# TIDA050024.net
KiCad netlist of a schematic drawn in Altium Designer
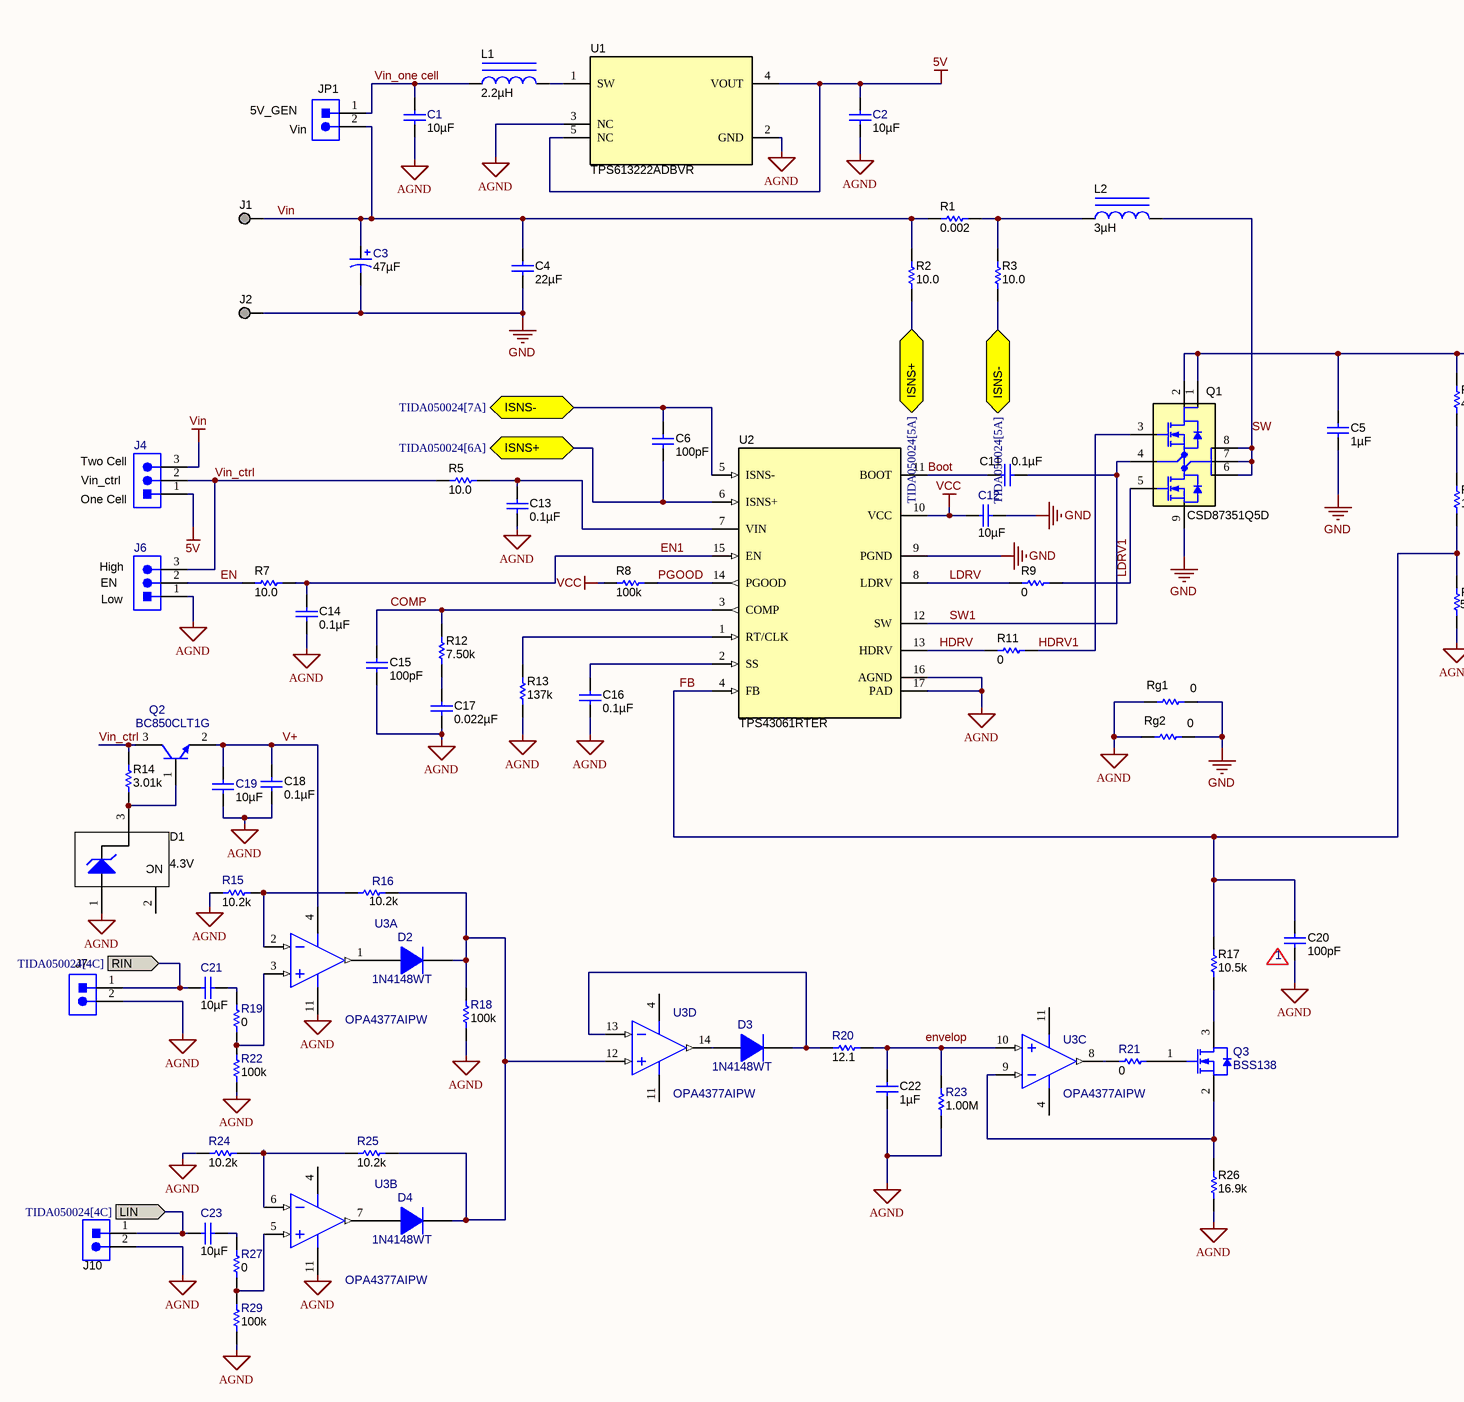
[diagram p0: TIDA050024.SchDoc, top middle]
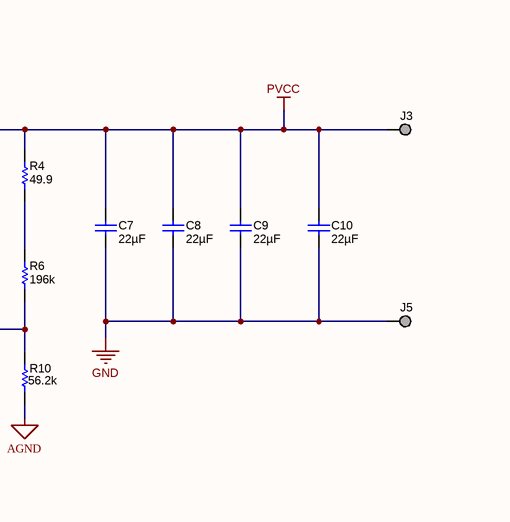
[diagram p1: TIDA050024.SchDoc, top right]
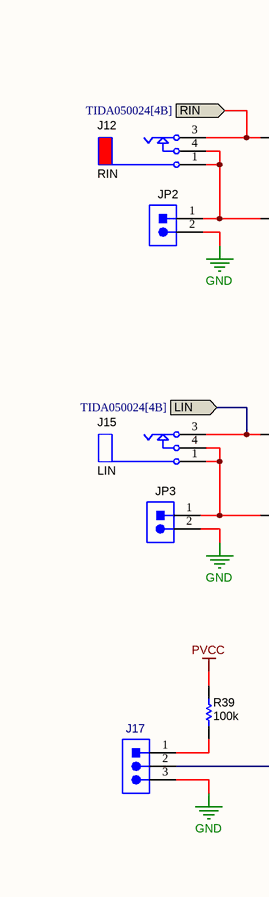
[diagram p2: TIDA050024.SchDoc, bottom left]
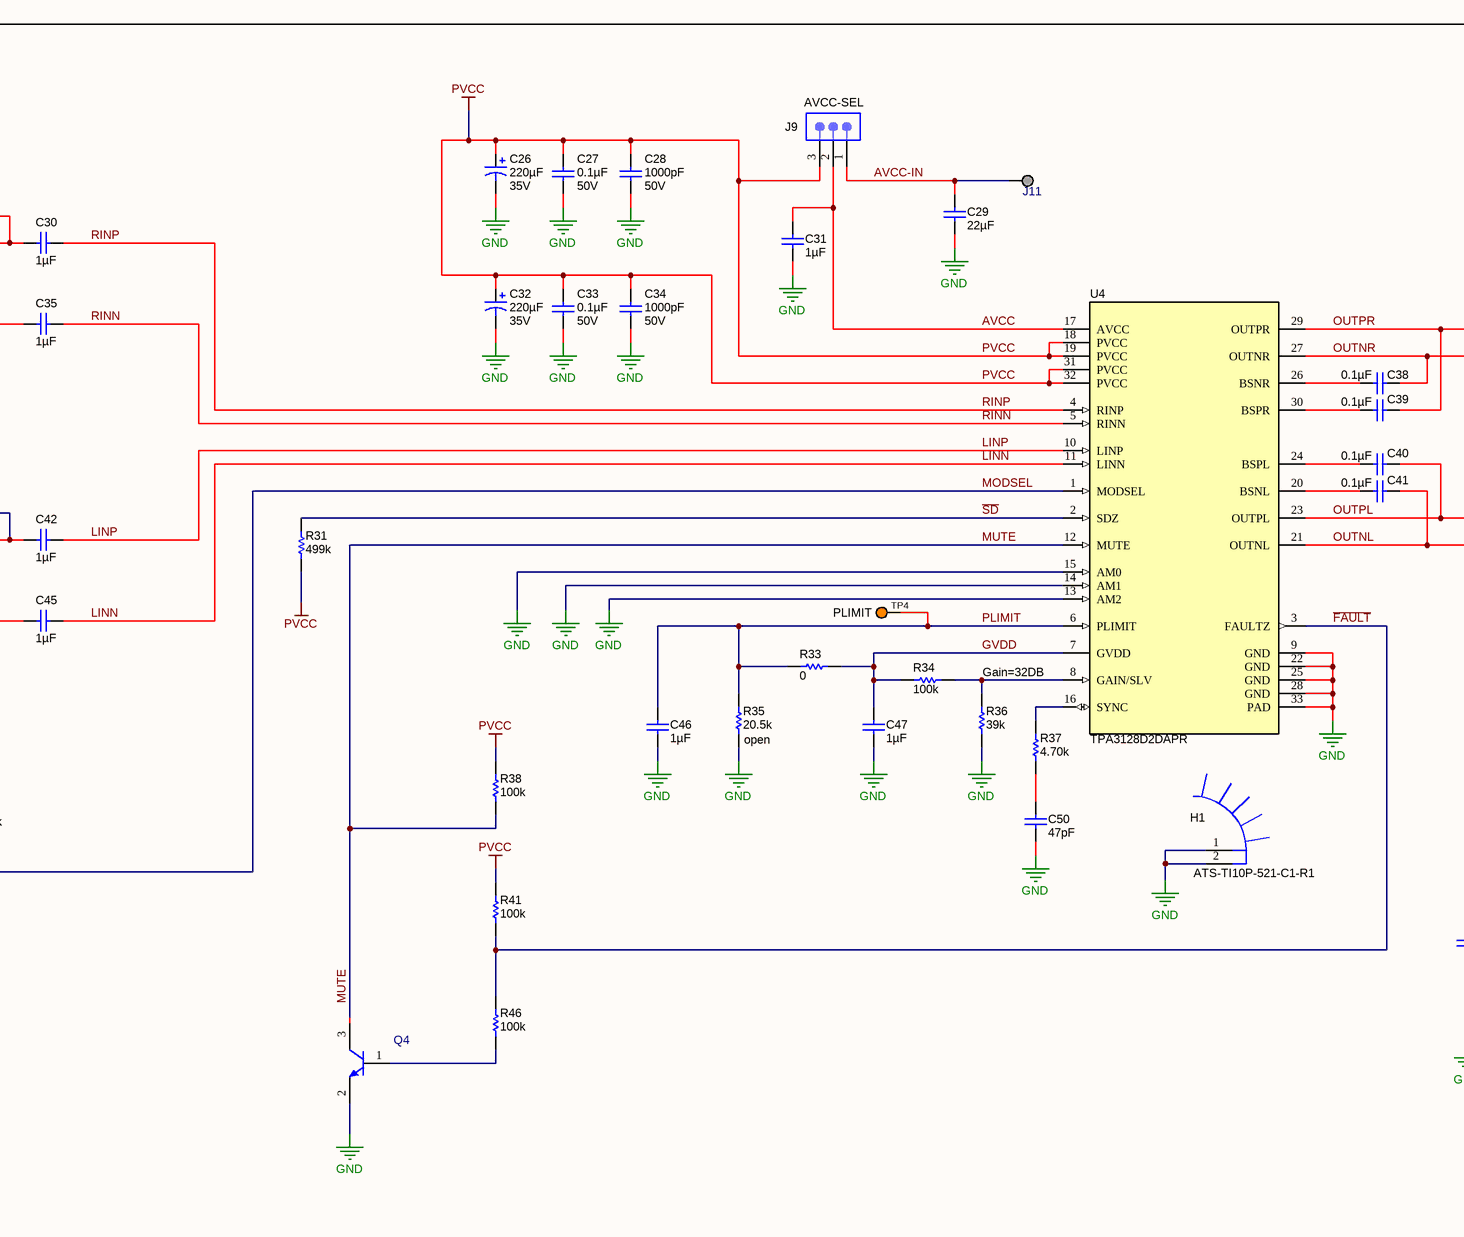
[diagram p3: TIDA050024.SchDoc, bottom middle]
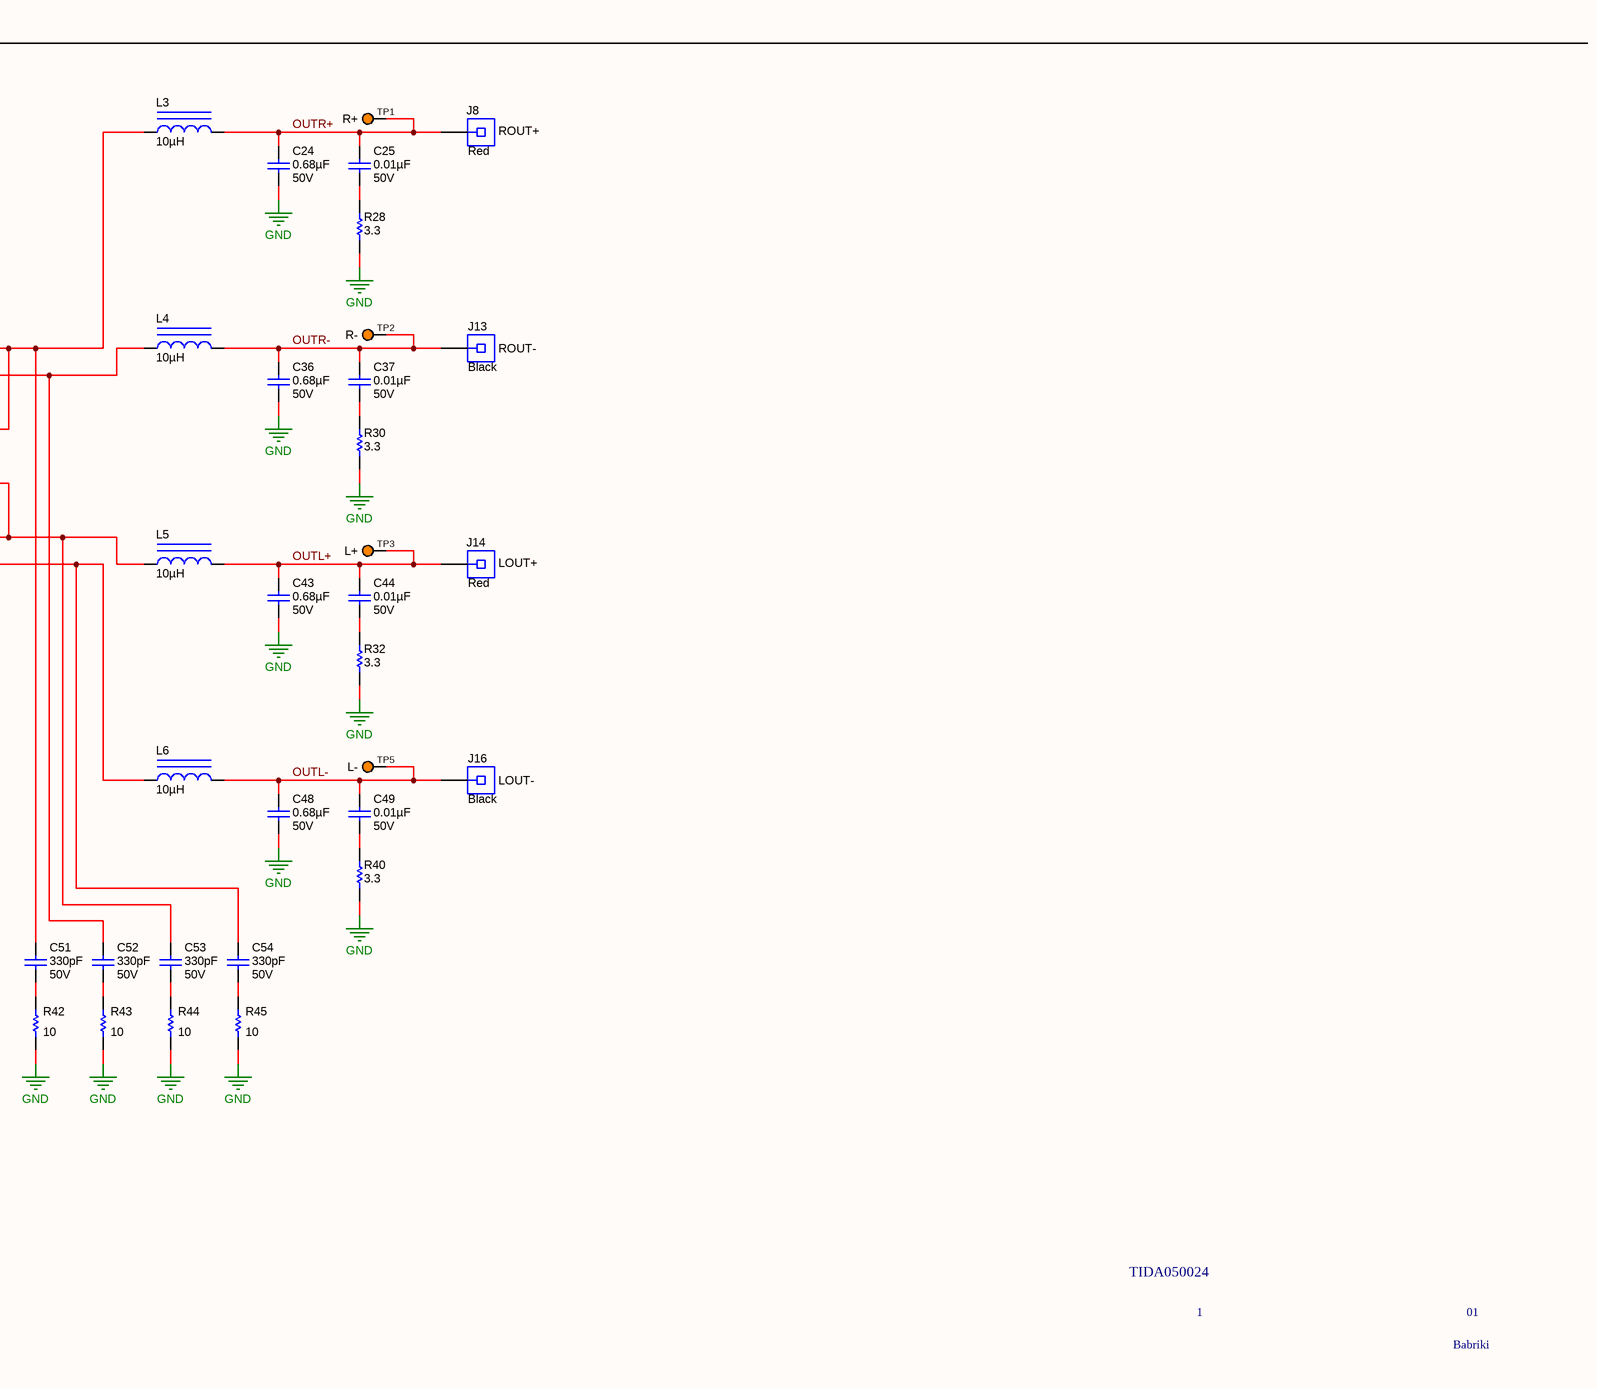
[diagram p4: TIDA050024.SchDoc, bottom right]

(export (version "E")
  (design (tool "Eeschema 10.0.6"))
  (components
    (comp (ref "C1")
      (value "GRM188R61E106MA73D")
      (footprint "0603")
      (description "CAP, CERM, 10 µF, 25 V, +/- 20%, X5R, 0603")
      (fields
        (field (name "VALUEDISPLAYED") "10µF")
        (field (name "MANUFACTURER") "MuRata")
        (field (name "PUBLISHER") "Texas Instruments")
      )
      (libsource (lib "Capacitor_Ceramic") (part "GRM188R61E106MA73D"))
    )
    (comp (ref "C2")
      (value "GRM188R61E106MA73D")
      (footprint "0603")
      (description "CAP, CERM, 10 µF, 25 V, +/- 20%, X5R, 0603")
      (fields
        (field (name "VALUEDISPLAYED") "10µF")
        (field (name "MANUFACTURER") "MuRata")
        (field (name "PUBLISHER") "Texas Instruments")
      )
      (libsource (lib "Capacitor_Ceramic") (part "GRM188R61E106MA73D"))
    )
    (comp (ref "C3")
      (value "T495D476M025ATE120")
      (footprint "7343-31")
      (description "CAP, TA, 47 µF, 25 V, +/- 20%, 0.12 ohm, SMD")
      (fields
        (field (name "VALUEDISPLAYED") "47µF")
        (field (name "MANUFACTURER") "Kemet")
        (field (name "PUBLISHER") "Texas Instruments")
      )
      (libsource (lib "Capacitor_Tantalum") (part "T495D476M025ATE120"))
    )
    (comp (ref "C4")
      (value "GRM32ER61E226KE15L")
      (footprint "1210_270")
      (description "CAP, CERM, 22 µF, 25 V, +/- 10%, X5R, 1210")
      (fields
        (field (name "VALUEDISPLAYED") "22µF")
        (field (name "MANUFACTURER") "MuRata")
        (field (name "PUBLISHER") "Texas Instruments")
      )
      (libsource (lib "Capacitor_Ceramic") (part "GRM32ER61E226KE15L"))
    )
    (comp (ref "C5")
      (value "C1005X5R1E105K050BC")
      (footprint "0402")
      (description "CAP, CERM, 1 µF, 25 V,+/- 10%, X5R, 0402")
      (fields
        (field (name "VALUEDISPLAYED") "1µF")
        (field (name "MANUFACTURER") "TDK")
        (field (name "PUBLISHER") "Texas Instruments")
      )
      (libsource (lib "Capacitor_Ceramic") (part "C1005X5R1E105K050BC"))
    )
    (comp (ref "C6")
      (value "GRM1555C1H101JA01D")
      (footprint "0402")
      (description "CAP, CERM, 100 pF, 50 V,+/- 5%, C0G/NP0, 0402")
      (fields
        (field (name "VALUEDISPLAYED") "100pF")
        (field (name "MANUFACTURER") "MuRata")
        (field (name "PUBLISHER") "Texas Instruments")
      )
      (libsource (lib "Capacitor_Ceramic") (part "GRM1555C1H101JA01D"))
    )
    (comp (ref "C7")
      (value "GRM32ER61E226KE15L")
      (footprint "1210_270")
      (description "CAP, CERM, 22 µF, 25 V, +/- 10%, X5R, 1210")
      (fields
        (field (name "VALUEDISPLAYED") "22µF")
        (field (name "MANUFACTURER") "MuRata")
        (field (name "PUBLISHER") "Texas Instruments")
      )
      (libsource (lib "Capacitor_Ceramic") (part "GRM32ER61E226KE15L"))
    )
    (comp (ref "C8")
      (value "GRM32ER61E226KE15L")
      (footprint "1210_270")
      (description "CAP, CERM, 22 µF, 25 V, +/- 10%, X5R, 1210")
      (fields
        (field (name "VALUEDISPLAYED") "22µF")
        (field (name "MANUFACTURER") "MuRata")
        (field (name "PUBLISHER") "Texas Instruments")
      )
      (libsource (lib "Capacitor_Ceramic") (part "GRM32ER61E226KE15L"))
    )
    (comp (ref "C9")
      (value "GRM32ER61E226KE15L")
      (footprint "1210_270")
      (description "CAP, CERM, 22 µF, 25 V, +/- 10%, X5R, 1210")
      (fields
        (field (name "VALUEDISPLAYED") "22µF")
        (field (name "MANUFACTURER") "MuRata")
        (field (name "PUBLISHER") "Texas Instruments")
      )
      (libsource (lib "Capacitor_Ceramic") (part "GRM32ER61E226KE15L"))
    )
    (comp (ref "C10")
      (value "GRM32ER61E226KE15L")
      (footprint "1210_270")
      (description "CAP, CERM, 22 µF, 25 V, +/- 10%, X5R, 1210")
      (fields
        (field (name "VALUEDISPLAYED") "22µF")
        (field (name "MANUFACTURER") "MuRata")
        (field (name "PUBLISHER") "Texas Instruments")
      )
      (libsource (lib "Capacitor_Ceramic") (part "GRM32ER61E226KE15L"))
    )
    (comp (ref "C11")
      (value "CGA2B3X7R1H104K050BB")
      (footprint "0402")
      (description "CAP, CERM, 0.1 µF, 50 V,+/- 10%, X7R, AEC-Q200 Grade 1, 0402")
      (fields
        (field (name "VALUEDISPLAYED") "0.1µF")
        (field (name "MANUFACTURER") "TDK")
        (field (name "PUBLISHER") "Texas Instruments")
      )
      (libsource (lib "Capacitor_Ceramic") (part "CGA2B3X7R1H104K050BB"))
    )
    (comp (ref "C12")
      (value "GRM188R61E106MA73D")
      (footprint "0603")
      (description "CAP, CERM, 10 µF, 25 V, +/- 20%, X5R, 0603")
      (fields
        (field (name "VALUEDISPLAYED") "10µF")
        (field (name "MANUFACTURER") "MuRata")
        (field (name "PUBLISHER") "Texas Instruments")
      )
      (libsource (lib "Capacitor_Ceramic") (part "GRM188R61E106MA73D"))
    )
    (comp (ref "C13")
      (value "CGA2B3X7R1H104K050BB")
      (footprint "0402")
      (description "CAP, CERM, 0.1 µF, 50 V,+/- 10%, X7R, AEC-Q200 Grade 1, 0402")
      (fields
        (field (name "VALUEDISPLAYED") "0.1µF")
        (field (name "MANUFACTURER") "TDK")
        (field (name "PUBLISHER") "Texas Instruments")
      )
      (libsource (lib "Capacitor_Ceramic") (part "CGA2B3X7R1H104K050BB"))
    )
    (comp (ref "C14")
      (value "CGA2B3X7R1H104K050BB")
      (footprint "0402")
      (description "CAP, CERM, 0.1 µF, 50 V,+/- 10%, X7R, AEC-Q200 Grade 1, 0402")
      (fields
        (field (name "VALUEDISPLAYED") "0.1µF")
        (field (name "MANUFACTURER") "TDK")
        (field (name "PUBLISHER") "Texas Instruments")
      )
      (libsource (lib "Capacitor_Ceramic") (part "CGA2B3X7R1H104K050BB"))
    )
    (comp (ref "C15")
      (value "GRM1555C1H101JA01D")
      (footprint "0402")
      (description "CAP, CERM, 100 pF, 50 V,+/- 5%, C0G/NP0, 0402")
      (fields
        (field (name "VALUEDISPLAYED") "100pF")
        (field (name "MANUFACTURER") "MuRata")
        (field (name "PUBLISHER") "Texas Instruments")
      )
      (libsource (lib "Capacitor_Ceramic") (part "GRM1555C1H101JA01D"))
    )
    (comp (ref "C16")
      (value "CGA2B3X7R1H104K050BB")
      (footprint "0402")
      (description "CAP, CERM, 0.1 µF, 50 V,+/- 10%, X7R, AEC-Q200 Grade 1, 0402")
      (fields
        (field (name "VALUEDISPLAYED") "0.1µF")
        (field (name "MANUFACTURER") "TDK")
        (field (name "PUBLISHER") "Texas Instruments")
      )
      (libsource (lib "Capacitor_Ceramic") (part "CGA2B3X7R1H104K050BB"))
    )
    (comp (ref "C17")
      (value "GCM155R71E223KA55D")
      (footprint "0402")
      (description "CAP, CERM, 0.022 µF, 25 V,+/- 10%, X7R, AEC-Q200 Grade 1, 0402")
      (fields
        (field (name "VALUEDISPLAYED") "0.022µF")
        (field (name "MANUFACTURER") "MuRata")
        (field (name "PUBLISHER") "Texas Instruments")
      )
      (libsource (lib "Capacitor_Ceramic") (part "GCM155R71E223KA55D"))
    )
    (comp (ref "C18")
      (value "CGA2B3X7R1H104K050BB")
      (footprint "0402")
      (description "CAP, CERM, 0.1 µF, 50 V,+/- 10%, X7R, AEC-Q200 Grade 1, 0402")
      (fields
        (field (name "VALUEDISPLAYED") "0.1µF")
        (field (name "MANUFACTURER") "TDK")
        (field (name "PUBLISHER") "Texas Instruments")
      )
      (libsource (lib "Capacitor_Ceramic") (part "CGA2B3X7R1H104K050BB"))
    )
    (comp (ref "C19")
      (value "GRM188R61E106MA73D")
      (footprint "0603")
      (description "CAP, CERM, 10 µF, 25 V, +/- 20%, X5R, 0603")
      (fields
        (field (name "VALUEDISPLAYED") "10µF")
        (field (name "MANUFACTURER") "MuRata")
        (field (name "PUBLISHER") "Texas Instruments")
      )
      (libsource (lib "Capacitor_Ceramic") (part "GRM188R61E106MA73D"))
    )
    (comp (ref "C20")
      (value "GRM1555C1H101JA01D")
      (footprint "0402")
      (description "CAP, CERM, 100 pF, 50 V,+/- 5%, C0G/NP0, 0402")
      (fields
        (field (name "VALUEDISPLAYED") "100pF")
        (field (name "MANUFACTURER") "MuRata")
        (field (name "PUBLISHER") "Texas Instruments")
      )
      (libsource (lib "Capacitor_Ceramic") (part "GRM1555C1H101JA01D"))
    )
    (comp (ref "C21")
      (value "GRM188R61E106MA73D")
      (footprint "0603")
      (description "CAP, CERM, 10 µF, 25 V, +/- 20%, X5R, 0603")
      (fields
        (field (name "VALUEDISPLAYED") "10µF")
        (field (name "MANUFACTURER") "MuRata")
        (field (name "PUBLISHER") "Texas Instruments")
      )
      (libsource (lib "Capacitor_Ceramic") (part "GRM188R61E106MA73D"))
    )
    (comp (ref "C22")
      (value "C1005X5R1E105K050BC")
      (footprint "0402")
      (description "CAP, CERM, 1 µF, 25 V,+/- 10%, X5R, 0402")
      (fields
        (field (name "VALUEDISPLAYED") "1µF")
        (field (name "MANUFACTURER") "TDK")
        (field (name "PUBLISHER") "Texas Instruments")
      )
      (libsource (lib "Capacitor_Ceramic") (part "C1005X5R1E105K050BC"))
    )
    (comp (ref "C23")
      (value "GRM188R61E106MA73D")
      (footprint "0603")
      (description "CAP, CERM, 10 µF, 25 V, +/- 20%, X5R, 0603")
      (fields
        (field (name "VALUEDISPLAYED") "10µF")
        (field (name "MANUFACTURER") "MuRata")
        (field (name "PUBLISHER") "Texas Instruments")
      )
      (libsource (lib "Capacitor_Ceramic") (part "GRM188R61E106MA73D"))
    )
    (comp (ref "C24")
      (value "GRM31MR71H684KA88L")
      (footprint "1206L")
      (description "CAP, CERM, 0.68 µF, 50 V, +/- 10%, X7R, 1206")
      (fields
        (field (name "VALUEDISPLAYED") "0.68µF")
        (field (name "MANUFACTURER") "MuRata")
        (field (name "VALUE2") "50V")
        (field (name "PUBLISHER") "Texas Instruments")
      )
      (libsource (lib "Capacitor_Ceramic") (part "GRM31MR71H684KA88L"))
    )
    (comp (ref "C25")
      (value "GRM188R71H103KA01D")
      (footprint "0603L")
      (description "CAP, CERM, 0.01 µF, 50 V, +/- 10%, X7R, 0603")
      (fields
        (field (name "VALUEDISPLAYED") "0.01µF")
        (field (name "MANUFACTURER") "MuRata")
        (field (name "VALUE2") "50V")
        (field (name "PUBLISHER") "Texas Instruments")
      )
      (libsource (lib "Capacitor_Ceramic") (part "GRM188R71H103KA01D"))
    )
    (comp (ref "C26")
      (value "EEU-FC1V221")
      (footprint "FC_1000x1250")
      (description "CAP, AL, 220 µF, 35 V, +/- 20%, 0.09 ohm, TH")
      (fields
        (field (name "VALUEDISPLAYED") "220µF")
        (field (name "MANUFACTURER") "Panasonic")
        (field (name "VALUE2") "35V")
        (field (name "PUBLISHER") "Texas Instruments")
      )
      (libsource (lib "Capacitor_Aluminum") (part "EEU-FC1V221"))
    )
    (comp (ref "C27")
      (value "GCM188R71H104KA57D")
      (footprint "0603L")
      (description "CAP, CERM, 0.1 µF, 50 V, +/- 10%, X7R, 0603")
      (fields
        (field (name "VALUEDISPLAYED") "0.1µF")
        (field (name "MANUFACTURER") "MuRata")
        (field (name "VALUE2") "50V")
        (field (name "PUBLISHER") "Texas Instruments")
      )
      (libsource (lib "Capacitor_Ceramic") (part "GCM188R71H104KA57D"))
    )
    (comp (ref "C28")
      (value "GRM1885C1H102JA01D")
      (footprint "0603L")
      (description "CAP, CERM, 1000 pF, 50 V, +/- 5%, C0G/NP0, 0603")
      (fields
        (field (name "VALUEDISPLAYED") "1000pF")
        (field (name "MANUFACTURER") "MuRata")
        (field (name "VALUE2") "50V")
        (field (name "PUBLISHER") "Texas Instruments")
      )
      (libsource (lib "Capacitor_Ceramic") (part "GRM1885C1H102JA01D"))
    )
    (comp (ref "C29")
      (value "GRM32ER61E226KE15L")
      (footprint "1210_270")
      (description "CAP, CERM, 22 µF, 25 V, +/- 10%, X5R, 1210")
      (fields
        (field (name "VALUEDISPLAYED") "22µF")
        (field (name "MANUFACTURER") "MuRata")
        (field (name "PUBLISHER") "Texas Instruments")
      )
      (libsource (lib "Capacitor_Ceramic") (part "GRM32ER61E226KE15L"))
    )
    (comp (ref "C30")
      (value "GRM188R61E105KA12D")
      (footprint "0603")
      (description "CAP, CERM, 1 µF, 25 V, +/- 10%, X5R, 0603")
      (fields
        (field (name "VALUEDISPLAYED") "1µF")
        (field (name "MANUFACTURER") "MuRata")
        (field (name "PUBLISHER") "Texas Instruments")
      )
      (libsource (lib "Capacitor_Ceramic") (part "GRM188R61E105KA12D"))
    )
    (comp (ref "C31")
      (value "GRM188R61E105KA12D")
      (footprint "0603")
      (description "CAP, CERM, 1 µF, 25 V, +/- 10%, X5R, 0603")
      (fields
        (field (name "VALUEDISPLAYED") "1µF")
        (field (name "MANUFACTURER") "MuRata")
        (field (name "PUBLISHER") "Texas Instruments")
      )
      (libsource (lib "Capacitor_Ceramic") (part "GRM188R61E105KA12D"))
    )
    (comp (ref "C32")
      (value "EEU-FC1V221")
      (footprint "FC_1000x1250")
      (description "CAP, AL, 220 µF, 35 V, +/- 20%, 0.09 ohm, TH")
      (fields
        (field (name "VALUEDISPLAYED") "220µF")
        (field (name "MANUFACTURER") "Panasonic")
        (field (name "VALUE2") "35V")
        (field (name "PUBLISHER") "Texas Instruments")
      )
      (libsource (lib "Capacitor_Aluminum") (part "EEU-FC1V221"))
    )
    (comp (ref "C33")
      (value "GCM188R71H104KA57D")
      (footprint "0603L")
      (description "CAP, CERM, 0.1 µF, 50 V, +/- 10%, X7R, 0603")
      (fields
        (field (name "VALUEDISPLAYED") "0.1µF")
        (field (name "MANUFACTURER") "MuRata")
        (field (name "VALUE2") "50V")
        (field (name "PUBLISHER") "Texas Instruments")
      )
      (libsource (lib "Capacitor_Ceramic") (part "GCM188R71H104KA57D"))
    )
    (comp (ref "C34")
      (value "GRM1885C1H102JA01D")
      (footprint "0603L")
      (description "CAP, CERM, 1000 pF, 50 V, +/- 5%, C0G/NP0, 0603")
      (fields
        (field (name "VALUEDISPLAYED") "1000pF")
        (field (name "MANUFACTURER") "MuRata")
        (field (name "VALUE2") "50V")
        (field (name "PUBLISHER") "Texas Instruments")
      )
      (libsource (lib "Capacitor_Ceramic") (part "GRM1885C1H102JA01D"))
    )
    (comp (ref "C35")
      (value "GRM188R61E105KA12D")
      (footprint "0603")
      (description "CAP, CERM, 1 µF, 25 V, +/- 10%, X5R, 0603")
      (fields
        (field (name "VALUEDISPLAYED") "1µF")
        (field (name "MANUFACTURER") "MuRata")
        (field (name "PUBLISHER") "Texas Instruments")
      )
      (libsource (lib "Capacitor_Ceramic") (part "GRM188R61E105KA12D"))
    )
    (comp (ref "C36")
      (value "GRM31MR71H684KA88L")
      (footprint "1206L")
      (description "CAP, CERM, 0.68 µF, 50 V, +/- 10%, X7R, 1206")
      (fields
        (field (name "VALUEDISPLAYED") "0.68µF")
        (field (name "MANUFACTURER") "MuRata")
        (field (name "VALUE2") "50V")
        (field (name "PUBLISHER") "Texas Instruments")
      )
      (libsource (lib "Capacitor_Ceramic") (part "GRM31MR71H684KA88L"))
    )
    (comp (ref "C37")
      (value "GRM188R71H103KA01D")
      (footprint "0603L")
      (description "CAP, CERM, 0.01 µF, 50 V, +/- 10%, X7R, 0603")
      (fields
        (field (name "VALUEDISPLAYED") "0.01µF")
        (field (name "MANUFACTURER") "MuRata")
        (field (name "VALUE2") "50V")
        (field (name "PUBLISHER") "Texas Instruments")
      )
      (libsource (lib "Capacitor_Ceramic") (part "GRM188R71H103KA01D"))
    )
    (comp (ref "C38")
      (value "GCM188R71H104KA57D")
      (footprint "0603L")
      (description "CAP, CERM, 0.1 µF, 50 V, +/- 10%, X7R, 0603")
      (fields
        (field (name "VALUEDISPLAYED") "0.1µF")
        (field (name "MANUFACTURER") "MuRata")
        (field (name "PUBLISHER") "Texas Instruments")
      )
      (libsource (lib "Capacitor_Ceramic") (part "GCM188R71H104KA57D"))
    )
    (comp (ref "C39")
      (value "GCM188R71H104KA57D")
      (footprint "0603L")
      (description "CAP, CERM, 0.1 µF, 50 V, +/- 10%, X7R, 0603")
      (fields
        (field (name "VALUEDISPLAYED") "0.1µF")
        (field (name "MANUFACTURER") "MuRata")
        (field (name "PUBLISHER") "Texas Instruments")
      )
      (libsource (lib "Capacitor_Ceramic") (part "GCM188R71H104KA57D"))
    )
    (comp (ref "C40")
      (value "GCM188R71H104KA57D")
      (footprint "0603L")
      (description "CAP, CERM, 0.1 µF, 50 V, +/- 10%, X7R, 0603")
      (fields
        (field (name "VALUEDISPLAYED") "0.1µF")
        (field (name "MANUFACTURER") "MuRata")
        (field (name "PUBLISHER") "Texas Instruments")
      )
      (libsource (lib "Capacitor_Ceramic") (part "GCM188R71H104KA57D"))
    )
    (comp (ref "C41")
      (value "GCM188R71H104KA57D")
      (footprint "0603L")
      (description "CAP, CERM, 0.1 µF, 50 V, +/- 10%, X7R, 0603")
      (fields
        (field (name "VALUEDISPLAYED") "0.1µF")
        (field (name "MANUFACTURER") "MuRata")
        (field (name "PUBLISHER") "Texas Instruments")
      )
      (libsource (lib "Capacitor_Ceramic") (part "GCM188R71H104KA57D"))
    )
    (comp (ref "C42")
      (value "GRM188R61E105KA12D")
      (footprint "0603")
      (description "CAP, CERM, 1 µF, 25 V, +/- 10%, X5R, 0603")
      (fields
        (field (name "VALUEDISPLAYED") "1µF")
        (field (name "MANUFACTURER") "MuRata")
        (field (name "PUBLISHER") "Texas Instruments")
      )
      (libsource (lib "Capacitor_Ceramic") (part "GRM188R61E105KA12D"))
    )
    (comp (ref "C43")
      (value "GRM31MR71H684KA88L")
      (footprint "1206L")
      (description "CAP, CERM, 0.68 µF, 50 V, +/- 10%, X7R, 1206")
      (fields
        (field (name "VALUEDISPLAYED") "0.68µF")
        (field (name "MANUFACTURER") "MuRata")
        (field (name "VALUE2") "50V")
        (field (name "PUBLISHER") "Texas Instruments")
      )
      (libsource (lib "Capacitor_Ceramic") (part "GRM31MR71H684KA88L"))
    )
    (comp (ref "C44")
      (value "GRM188R71H103KA01D")
      (footprint "0603L")
      (description "CAP, CERM, 0.01 µF, 50 V, +/- 10%, X7R, 0603")
      (fields
        (field (name "VALUEDISPLAYED") "0.01µF")
        (field (name "MANUFACTURER") "MuRata")
        (field (name "VALUE2") "50V")
        (field (name "PUBLISHER") "Texas Instruments")
      )
      (libsource (lib "Capacitor_Ceramic") (part "GRM188R71H103KA01D"))
    )
    (comp (ref "C45")
      (value "GRM188R61E105KA12D")
      (footprint "0603")
      (description "CAP, CERM, 1 µF, 25 V, +/- 10%, X5R, 0603")
      (fields
        (field (name "VALUEDISPLAYED") "1µF")
        (field (name "MANUFACTURER") "MuRata")
        (field (name "PUBLISHER") "Texas Instruments")
      )
      (libsource (lib "Capacitor_Ceramic") (part "GRM188R61E105KA12D"))
    )
    (comp (ref "C46")
      (value "GRM188R61E105KA12D")
      (footprint "0603")
      (description "CAP, CERM, 1 µF, 25 V, +/- 10%, X5R, 0603")
      (fields
        (field (name "VALUEDISPLAYED") "1µF")
        (field (name "MANUFACTURER") "MuRata")
        (field (name "PUBLISHER") "Texas Instruments")
      )
      (libsource (lib "Capacitor_Ceramic") (part "GRM188R61E105KA12D"))
    )
    (comp (ref "C47")
      (value "GRM188R61E105KA12D")
      (footprint "0603")
      (description "CAP, CERM, 1 µF, 25 V, +/- 10%, X5R, 0603")
      (fields
        (field (name "VALUEDISPLAYED") "1µF")
        (field (name "MANUFACTURER") "MuRata")
        (field (name "PUBLISHER") "Texas Instruments")
      )
      (libsource (lib "Capacitor_Ceramic") (part "GRM188R61E105KA12D"))
    )
    (comp (ref "C48")
      (value "GRM31MR71H684KA88L")
      (footprint "1206L")
      (description "CAP, CERM, 0.68 µF, 50 V, +/- 10%, X7R, 1206")
      (fields
        (field (name "VALUEDISPLAYED") "0.68µF")
        (field (name "MANUFACTURER") "MuRata")
        (field (name "VALUE2") "50V")
        (field (name "PUBLISHER") "Texas Instruments")
      )
      (libsource (lib "Capacitor_Ceramic") (part "GRM31MR71H684KA88L"))
    )
    (comp (ref "C49")
      (value "GRM188R71H103KA01D")
      (footprint "0603L")
      (description "CAP, CERM, 0.01 µF, 50 V, +/- 10%, X7R, 0603")
      (fields
        (field (name "VALUEDISPLAYED") "0.01µF")
        (field (name "MANUFACTURER") "MuRata")
        (field (name "VALUE2") "50V")
        (field (name "PUBLISHER") "Texas Instruments")
      )
      (libsource (lib "Capacitor_Ceramic") (part "GRM188R71H103KA01D"))
    )
    (comp (ref "C50")
      (value "GRM1885C1H470JA01D")
      (footprint "0603L")
      (description "CAP, CERM, 47 pF, 50 V, +/- 5%, C0G/NP0, 0603")
      (fields
        (field (name "VALUEDISPLAYED") "47pF")
        (field (name "MANUFACTURER") "MuRata")
        (field (name "PUBLISHER") "Texas Instruments")
      )
      (libsource (lib "Capacitor_Ceramic") (part "GRM1885C1H470JA01D"))
    )
    (comp (ref "C51")
      (value "GRM1885C1H331JA01D")
      (footprint "0603L")
      (description "CAP, CERM, 330 pF, 50 V, +/- 5%, C0G/NP0, 0603")
      (fields
        (field (name "VALUEDISPLAYED") "330pF")
        (field (name "MANUFACTURER") "MuRata")
        (field (name "VALUE2") "50V")
        (field (name "PUBLISHER") "Texas Instruments")
      )
      (libsource (lib "Capacitor_Ceramic") (part "GRM1885C1H331JA01D"))
    )
    (comp (ref "C52")
      (value "GRM1885C1H331JA01D")
      (footprint "0603L")
      (description "CAP, CERM, 330 pF, 50 V, +/- 5%, C0G/NP0, 0603")
      (fields
        (field (name "VALUEDISPLAYED") "330pF")
        (field (name "MANUFACTURER") "MuRata")
        (field (name "VALUE2") "50V")
        (field (name "PUBLISHER") "Texas Instruments")
      )
      (libsource (lib "Capacitor_Ceramic") (part "GRM1885C1H331JA01D"))
    )
    (comp (ref "C53")
      (value "GRM1885C1H331JA01D")
      (footprint "0603L")
      (description "CAP, CERM, 330 pF, 50 V, +/- 5%, C0G/NP0, 0603")
      (fields
        (field (name "VALUEDISPLAYED") "330pF")
        (field (name "MANUFACTURER") "MuRata")
        (field (name "VALUE2") "50V")
        (field (name "PUBLISHER") "Texas Instruments")
      )
      (libsource (lib "Capacitor_Ceramic") (part "GRM1885C1H331JA01D"))
    )
    (comp (ref "C54")
      (value "GRM1885C1H331JA01D")
      (footprint "0603L")
      (description "CAP, CERM, 330 pF, 50 V, +/- 5%, C0G/NP0, 0603")
      (fields
        (field (name "VALUEDISPLAYED") "330pF")
        (field (name "MANUFACTURER") "MuRata")
        (field (name "VALUE2") "50V")
        (field (name "PUBLISHER") "Texas Instruments")
      )
      (libsource (lib "Capacitor_Ceramic") (part "GRM1885C1H331JA01D"))
    )
    (comp (ref "D1")
      (value "4.3V")
      (footprint "SOT-23")
      (description "Diode, Zener, 4.3 V, 225 mW, SOT-23")
      (fields
        (field (name "MANUFACTURER") "ON Semiconductor")
        (field (name "PARTNUMBER") "BZX84C4V3LT1G")
        (field (name "PUBLISHER") "Texas Instruments")
      )
      (libsource (lib "ZenerDiodes") (part "BZX84C4V3LT1G"))
    )
    (comp (ref "D2")
      (value "1N4148WT")
      (footprint "Fairchild_SOD-523F")
      (description "Diode, Switching, 75 V, 0.3 A, SMD, 2-Leads, Body 1.2x0.8mm")
      (fields
        (field (name "MANUFACTURER") "Fairchild Semiconductor")
        (field (name "PUBLISHER") "Texas Instruments")
      )
      (libsource (lib "Diode") (part "1N4148WT"))
    )
    (comp (ref "D3")
      (value "1N4148WT")
      (footprint "Fairchild_SOD-523F")
      (description "Diode, Switching, 75 V, 0.3 A, SMD, 2-Leads, Body 1.2x0.8mm")
      (fields
        (field (name "MANUFACTURER") "Fairchild Semiconductor")
        (field (name "PUBLISHER") "Texas Instruments")
      )
      (libsource (lib "Diode") (part "1N4148WT"))
    )
    (comp (ref "D4")
      (value "1N4148WT")
      (footprint "Fairchild_SOD-523F")
      (description "Diode, Switching, 75 V, 0.3 A, SMD, 2-Leads, Body 1.2x0.8mm")
      (fields
        (field (name "MANUFACTURER") "Fairchild Semiconductor")
        (field (name "PUBLISHER") "Texas Instruments")
      )
      (libsource (lib "Diode") (part "1N4148WT"))
    )
    (comp (ref "H1")
      (value "ATS-TI10P-521-C1-R1")
      (footprint "HSINK_ATS-TI10P-521-C1-R1")
      (description "Heatsink FOR TI MOD, 50x13.9mm")
      (fields
        (field (name "MANUFACTURER") "Advanced Thermal Solutions")
        (field (name "SYMBOLCREATOR") "a0799628")
        (field (name "PUBLISHER") "Texas Instruments")
      )
      (libsource (lib "Hardware") (part "ATS-TI10P-521-C1-R1"))
    )
    (comp (ref "J1")
      (value "1502-2")
      (footprint "Keystone1502-2")
      (description "Terminal, Turret, TH, Double")
      (fields (field (name "MANUFACTURER") "Keystone") (field (name "PUBLISHER") "Texas Instruments"))
      (libsource (lib "Altium Vault - TI") (part "CMP-0055113-1"))
    )
    (comp (ref "J2")
      (value "1502-2")
      (footprint "Keystone1502-2")
      (description "Terminal, Turret, TH, Double")
      (fields (field (name "MANUFACTURER") "Keystone") (field (name "PUBLISHER") "Texas Instruments"))
      (libsource (lib "Altium Vault - TI") (part "CMP-0055113-1"))
    )
    (comp (ref "J3")
      (value "1502-2")
      (footprint "Keystone1502-2")
      (description "Terminal, Turret, TH, Double")
      (fields (field (name "MANUFACTURER") "Keystone") (field (name "PUBLISHER") "Texas Instruments"))
      (libsource (lib "Altium Vault - TI") (part "CMP-0055113-1"))
    )
    (comp (ref "J4")
      (value "TSW-103-07-G-S")
      (footprint "TSW-103-07-G-S")
      (description "Header, 100mil, 3x1, Gold, TH")
      (fields
        (field (name "MANUFACTURER") "Samtec")
        (field (name "SYMBOLCREATOR") "a0799628")
        (field (name "PUBLISHER") "Texas Instruments")
      )
      (libsource (lib "Connectors_Samtec") (part "TSW-103-07-G-S"))
    )
    (comp (ref "J5")
      (value "1502-2")
      (footprint "Keystone1502-2")
      (description "Terminal, Turret, TH, Double")
      (fields (field (name "MANUFACTURER") "Keystone") (field (name "PUBLISHER") "Texas Instruments"))
      (libsource (lib "Altium Vault - TI") (part "CMP-0055113-1"))
    )
    (comp (ref "J6")
      (value "TSW-103-07-G-S")
      (footprint "TSW-103-07-G-S")
      (description "Header, 100mil, 3x1, Gold, TH")
      (fields
        (field (name "MANUFACTURER") "Samtec")
        (field (name "SYMBOLCREATOR") "a0799628")
        (field (name "PUBLISHER") "Texas Instruments")
      )
      (libsource (lib "Connectors_Samtec") (part "TSW-103-07-G-S"))
    )
    (comp (ref "J7")
      (value "TSW-102-07-G-S")
      (footprint "TSW-102-07-G-S")
      (description "Header, 100mil, 2x1, Gold, TH")
      (fields
        (field (name "MANUFACTURER") "Samtec")
        (field (name "SYMBOLCREATOR") "a0412235")
        (field (name "PUBLISHER") "Texas Instruments")
      )
      (libsource (lib "Connectors_Samtec") (part "TSW-102-07-G-S"))
    )
    (comp (ref "J8")
      (value "ROUT+")
      (footprint "Keystone_7006")
      (description "Binding Post, RED, TH")
      (fields
        (field (name "PARTNUMBER") "7006")
        (field (name "MANUFACTURER") "Keystone")
        (field (name "SHELL COLOR") "Red")
        (field (name "SYMBOLCREATOR") "a0799628")
        (field (name "PUBLISHER") "Texas Instruments")
      )
      (libsource (lib "Connectors_Keystone") (part "7006"))
    )
    (comp (ref "J9")
      (value "AVCC-SEL")
      (footprint "PBC03SAAN")
      (description "Header, 100mil, 3x1, Gold, TH")
      (fields
        (field (name "PARTNUMBER") "PBC03SAAN")
        (field (name "MANUFACTURER") "Sullins Connector Solutions")
        (field (name "PUBLISHER") "Texas Instruments")
      )
      (libsource (lib "Connectors_Sullins") (part "PBC03SAAN"))
    )
    (comp (ref "J10")
      (value "TSW-102-07-G-S")
      (footprint "TSW-102-07-G-S")
      (description "Header, 100mil, 2x1, Gold, TH")
      (fields
        (field (name "MANUFACTURER") "Samtec")
        (field (name "SYMBOLCREATOR") "a0412235")
        (field (name "PUBLISHER") "Texas Instruments")
      )
      (libsource (lib "Connectors_Samtec") (part "TSW-102-07-G-S"))
    )
    (comp (ref "J11")
      (value "Suggest using a net name here")
      (footprint "Keystone1502-2")
      (description "Terminal, Turret, TH, Double")
      (fields
        (field (name "PARTNUMBER") "1502-2")
        (field (name "MANUFACTURER") "Keystone")
        (field (name "PUBLISHER") "Texas Instruments")
      )
      (libsource (lib "Connectors_Keystone") (part "1502-2"))
    )
    (comp (ref "J12")
      (value "RIN")
      (footprint "Keystone_971")
      (description "RCA Jack, Red, R/A, TH")
      (fields
        (field (name "PARTNUMBER") "971")
        (field (name "MANUFACTURER") "Keystone")
        (field (name "SYMBOLCREATOR") "Altium")
        (field (name "PUBLISHER") "Texas Instruments")
      )
      (libsource (lib "Connectors_Keystone") (part "971"))
    )
    (comp (ref "J13")
      (value "ROUT-")
      (footprint "Keystone_7007")
      (description "Binding Post, BLACK, TH")
      (fields
        (field (name "PARTNUMBER") "7007")
        (field (name "MANUFACTURER") "Keystone")
        (field (name "SHELL COLOR") "Black")
        (field (name "SYMBOLCREATOR") "a0799628")
        (field (name "PUBLISHER") "Texas Instruments")
      )
      (libsource (lib "Connectors_Keystone") (part "7007"))
    )
    (comp (ref "J14")
      (value "LOUT+")
      (footprint "Keystone_7006")
      (description "Binding Post, RED, TH")
      (fields
        (field (name "PARTNUMBER") "7006")
        (field (name "MANUFACTURER") "Keystone")
        (field (name "SHELL COLOR") "Red")
        (field (name "SYMBOLCREATOR") "a0799628")
        (field (name "PUBLISHER") "Texas Instruments")
      )
      (libsource (lib "Connectors_Keystone") (part "7006"))
    )
    (comp (ref "J15")
      (value "LIN")
      (footprint "Keystone_970")
      (description "RCA Jack, White, R/A, TH")
      (fields
        (field (name "PARTNUMBER") "970")
        (field (name "MANUFACTURER") "Keystone")
        (field (name "SYMBOLCREATOR") "Altium")
        (field (name "PUBLISHER") "Texas Instruments")
      )
      (libsource (lib "Connectors_Keystone") (part "970"))
    )
    (comp (ref "J16")
      (value "LOUT-")
      (footprint "Keystone_7007")
      (description "Binding Post, BLACK, TH")
      (fields
        (field (name "PARTNUMBER") "7007")
        (field (name "MANUFACTURER") "Keystone")
        (field (name "SHELL COLOR") "Black")
        (field (name "SYMBOLCREATOR") "a0799628")
        (field (name "PUBLISHER") "Texas Instruments")
      )
      (libsource (lib "Connectors_Keystone") (part "7007"))
    )
    (comp (ref "J17")
      (value "TSW-103-07-G-S")
      (footprint "TSW-103-07-G-S")
      (description "Header, 100mil, 3x1, Gold, TH")
      (fields
        (field (name "MANUFACTURER") "Samtec")
        (field (name "SYMBOLCREATOR") "a0799628")
        (field (name "PUBLISHER") "Texas Instruments")
      )
      (libsource (lib "") (part "TSW-103-07-G-S_1"))
    )
    (comp (ref "JP1")
      (value "TSW-102-07-G-S")
      (footprint "TSW-102-07-G-S")
      (description "Header, 100mil, 2x1, Gold, TH")
      (fields
        (field (name "MANUFACTURER") "Samtec")
        (field (name "SYMBOLCREATOR") "a0412235")
        (field (name "PUBLISHER") "Texas Instruments")
      )
      (libsource (lib "Connectors_Samtec") (part "TSW-102-07-G-S"))
    )
    (comp (ref "JP2")
      (value "TSW-102-07-G-S")
      (footprint "TSW-102-07-G-S")
      (description "Header, 100mil, 2x1, Gold, TH")
      (fields
        (field (name "MANUFACTURER") "Samtec")
        (field (name "SYMBOLCREATOR") "a0412235")
        (field (name "PUBLISHER") "Texas Instruments")
      )
      (libsource (lib "Connectors_Samtec") (part "TSW-102-07-G-S"))
    )
    (comp (ref "JP3")
      (value "TSW-102-07-G-S")
      (footprint "TSW-102-07-G-S")
      (description "Header, 100mil, 2x1, Gold, TH")
      (fields
        (field (name "MANUFACTURER") "Samtec")
        (field (name "SYMBOLCREATOR") "a0412235")
        (field (name "PUBLISHER") "Texas Instruments")
      )
      (libsource (lib "Connectors_Samtec") (part "TSW-102-07-G-S"))
    )
    (comp (ref "L1")
      (value "DFE252012F-2R2M=P2")
      (footprint "DFE252012C")
      (description "Inductor, Shielded, Powdered Iron, 2.2 µH, 2.3 A, 0.082 ohm, SMD")
      (fields
        (field (name "VALUEDISPLAYED") "2.2µH")
        (field (name "MANUFACTURER") "MuRata Toko")
        (field (name "PUBLISHER") "Texas Instruments")
      )
      (libsource (lib "Inductor_Toko") (part "DFE252012F-2R2M=P2"))
    )
    (comp (ref "L2")
      (value "XAL1350-302MEB")
      (footprint "XAL1350")
      (description "Inductor, Shielded, Composite, 3 µH, 21 A, 0.0059 ohm, SMD")
      (fields
        (field (name "VALUEDISPLAYED") "3µH")
        (field (name "MANUFACTURER") "Coilcraft")
        (field (name "PUBLISHER") "Texas Instruments")
      )
      (libsource (lib "Inductor_Coilcraft") (part "XAL1350-302MEB"))
    )
    (comp (ref "L3")
      (value "SRT8045-103MEB")
      (footprint "SRT8045")
      (description "Inductor, Shielded, Ferrite, 10 µH, 4.2 A, 0.037 ohm, AEC-Q200 Grade 1, SMD")
      (fields
        (field (name "VALUEDISPLAYED") "10µH")
        (field (name "MANUFACTURER") "Coilcraft")
        (field (name "PUBLISHER") "Texas Instruments")
      )
      (libsource (lib "Inductor_Coilcraft") (part "SRT8045-103MEB"))
    )
    (comp (ref "L4")
      (value "SRT8045-103MEB")
      (footprint "SRT8045")
      (description "Inductor, Shielded, Ferrite, 10 µH, 4.2 A, 0.037 ohm, AEC-Q200 Grade 1, SMD")
      (fields
        (field (name "VALUEDISPLAYED") "10µH")
        (field (name "MANUFACTURER") "Coilcraft")
        (field (name "PUBLISHER") "Texas Instruments")
      )
      (libsource (lib "Inductor_Coilcraft") (part "SRT8045-103MEB"))
    )
    (comp (ref "L5")
      (value "SRT8045-103MEB")
      (footprint "SRT8045")
      (description "Inductor, Shielded, Ferrite, 10 µH, 4.2 A, 0.037 ohm, AEC-Q200 Grade 1, SMD")
      (fields
        (field (name "VALUEDISPLAYED") "10µH")
        (field (name "MANUFACTURER") "Coilcraft")
        (field (name "PUBLISHER") "Texas Instruments")
      )
      (libsource (lib "Inductor_Coilcraft") (part "SRT8045-103MEB"))
    )
    (comp (ref "L6")
      (value "SRT8045-103MEB")
      (footprint "SRT8045")
      (description "Inductor, Shielded, Ferrite, 10 µH, 4.2 A, 0.037 ohm, AEC-Q200 Grade 1, SMD")
      (fields
        (field (name "VALUEDISPLAYED") "10µH")
        (field (name "MANUFACTURER") "Coilcraft")
        (field (name "PUBLISHER") "Texas Instruments")
      )
      (libsource (lib "Inductor_Coilcraft") (part "SRT8045-103MEB"))
    )
    (comp (ref "Q1")
      (value "CSD87351Q5D")
      (footprint "DQY0008A")
      (description "MOSFET, 2-CH, N-CH, 30 V, 35 A, DQY0008A (LSON-CLIP-8)")
      (fields
        (field (name "MANUFACTURER") "Texas Instruments")
        (field (name "SYMBOLCREATOR") "a0799628")
        (field (name "PUBLISHER") "Texas Instruments")
      )
      (libsource (lib "FETs") (part "CSD87351Q5D"))
    )
    (comp (ref "Q2")
      (value "BC850CLT1G")
      (footprint "SOT-23")
      (description "Transistor, NPN, 45 V, 0.1 A, SOT-23")
      (fields (field (name "MANUFACTURER") "ON Semiconductor") (field (name "PUBLISHER") "Texas Instruments"))
      (libsource (lib "Bipolar_Transistor") (part "BC850CLT1G, ON Semiconductor"))
    )
    (comp (ref "Q3")
      (value "BSS138")
      (footprint "SOT-23")
      (description "MOSFET, N-CH, 50 V, 0.22 A, SOT-23")
      (fields
        (field (name "MANUFACTURER") "Fairchild Semiconductor")
        (field (name "PUBLISHER") "Texas Instruments")
      )
      (libsource (lib "FETs") (part "BSS138"))
    )
    (comp (ref "Q4")
      (value "BC850CLT1G")
      (footprint "SOT-23")
      (description "Transistor, NPN, 45 V, 0.1 A, SOT-23")
      (fields (field (name "MANUFACTURER") "ON Semiconductor") (field (name "PUBLISHER") "Texas Instruments"))
      (libsource (lib "Bipolar_Transistor") (part "BC850CLT1G, ON Semiconductor"))
    )
    (comp (ref "R1")
      (value "CSNL2512FT2L00")
      (footprint "2512")
      (description "RES, 0.002, 1%, 2 W, 2512")
      (fields
        (field (name "VALUEDISPLAYED") "0.002")
        (field (name "MANUFACTURER") "Stackpole Electronics Inc")
        (field (name "PUBLISHER") "Texas Instruments")
      )
      (libsource (lib "Resistor_2512") (part "CSNL2512FT2L00"))
    )
    (comp (ref "R2")
      (value "CRCW040210R0FKED")
      (footprint "0402")
      (description "RES, 10.0, 1%, 0.063 W, 0402")
      (fields
        (field (name "VALUEDISPLAYED") "10.0")
        (field (name "MANUFACTURER") "Vishay-Dale")
        (field (name "PUBLISHER") "Texas Instruments")
      )
      (libsource (lib "Resistor_0402") (part "CRCW040210R0FKED"))
    )
    (comp (ref "R3")
      (value "CRCW040210R0FKED")
      (footprint "0402")
      (description "RES, 10.0, 1%, 0.063 W, 0402")
      (fields
        (field (name "VALUEDISPLAYED") "10.0")
        (field (name "MANUFACTURER") "Vishay-Dale")
        (field (name "PUBLISHER") "Texas Instruments")
      )
      (libsource (lib "Resistor_0402") (part "CRCW040210R0FKED"))
    )
    (comp (ref "R4")
      (value "CRCW040249R9FKED")
      (footprint "0402")
      (description "RES, 49.9, 1%, 0.063 W, 0402")
      (fields
        (field (name "VALUEDISPLAYED") "49.9")
        (field (name "MANUFACTURER") "Vishay-Dale")
        (field (name "PUBLISHER") "Texas Instruments")
      )
      (libsource (lib "Resistor_0402") (part "CRCW040249R9FKED"))
    )
    (comp (ref "R5")
      (value "CRCW040210R0FKED")
      (footprint "0402")
      (description "RES, 10.0, 1%, 0.063 W, 0402")
      (fields
        (field (name "VALUEDISPLAYED") "10.0")
        (field (name "MANUFACTURER") "Vishay-Dale")
        (field (name "PUBLISHER") "Texas Instruments")
      )
      (libsource (lib "Resistor_0402") (part "CRCW040210R0FKED"))
    )
    (comp (ref "R6")
      (value "CRCW0402196KFKED")
      (footprint "0402")
      (description "RES, 196 k, 1%, 0.063 W, 0402")
      (fields
        (field (name "VALUEDISPLAYED") "196k")
        (field (name "MANUFACTURER") "Vishay-Dale")
        (field (name "PUBLISHER") "Texas Instruments")
      )
      (libsource (lib "Resistor_0402") (part "CRCW0402196KFKED"))
    )
    (comp (ref "R7")
      (value "CRCW040210R0FKED")
      (footprint "0402")
      (description "RES, 10.0, 1%, 0.063 W, 0402")
      (fields
        (field (name "VALUEDISPLAYED") "10.0")
        (field (name "MANUFACTURER") "Vishay-Dale")
        (field (name "PUBLISHER") "Texas Instruments")
      )
      (libsource (lib "Resistor_0402") (part "CRCW040210R0FKED"))
    )
    (comp (ref "R8")
      (value "CRCW0402100KFKED")
      (footprint "0402")
      (description "RES, 100 k, 1%, 0.063 W, 0402")
      (fields
        (field (name "VALUEDISPLAYED") "100k")
        (field (name "MANUFACTURER") "Vishay-Dale")
        (field (name "PUBLISHER") "Texas Instruments")
      )
      (libsource (lib "Resistor_0402") (part "CRCW0402100KFKED"))
    )
    (comp (ref "R9")
      (value "RCS06030000Z0EA")
      (footprint "0603")
      (description "RES, 0, 0%, 0.25 W, AEC-Q200 Grade 0, 0603")
      (fields (field (name "MANUFACTURER") "Vishay-Dale") (field (name "VALUEDISPLAYED") "0"))
      (libsource (lib "Altium Vault - TI") (part "CMP-0081973-1"))
    )
    (comp (ref "R10")
      (value "CRCW040256K2FKED")
      (footprint "0402")
      (description "RES, 56.2 k, 1%, 0.063 W, 0402")
      (fields
        (field (name "VALUEDISPLAYED") "56.2k")
        (field (name "MANUFACTURER") "Vishay-Dale")
        (field (name "PUBLISHER") "Texas Instruments")
      )
      (libsource (lib "Resistor_0402") (part "CRCW040256K2FKED"))
    )
    (comp (ref "R11")
      (value "RCS06030000Z0EA")
      (footprint "0603")
      (description "RES, 0, 0%, 0.25 W, AEC-Q200 Grade 0, 0603")
      (fields (field (name "MANUFACTURER") "Vishay-Dale") (field (name "VALUEDISPLAYED") "0"))
      (libsource (lib "Altium Vault - TI") (part "Resistor"))
    )
    (comp (ref "R12")
      (value "CRCW04027K50FKED")
      (footprint "0402")
      (description "RES, 7.50 k, 1%, 0.063 W, 0402")
      (fields
        (field (name "VALUEDISPLAYED") "7.50k")
        (field (name "MANUFACTURER") "Vishay-Dale")
        (field (name "PUBLISHER") "Texas Instruments")
      )
      (libsource (lib "Resistor_0402") (part "CRCW04027K50FKED"))
    )
    (comp (ref "R13")
      (value "CRCW0402137KFKED")
      (footprint "0402")
      (description "RES, 137 k, 1%, 0.063 W, 0402")
      (fields
        (field (name "VALUEDISPLAYED") "137k")
        (field (name "MANUFACTURER") "Vishay-Dale")
        (field (name "PUBLISHER") "Texas Instruments")
      )
      (libsource (lib "Resistor_0402") (part "CRCW0402137KFKED"))
    )
    (comp (ref "R14")
      (value "CRCW04023K01FKED")
      (footprint "0402")
      (description "RES, 3.01 k, 1%, 0.063 W, 0402")
      (fields
        (field (name "VALUEDISPLAYED") "3.01k")
        (field (name "MANUFACTURER") "Vishay-Dale")
        (field (name "PUBLISHER") "Texas Instruments")
      )
      (libsource (lib "Resistor_0402") (part "CRCW04023K01FKED"))
    )
    (comp (ref "R15")
      (value "CRCW040210K2FKED")
      (footprint "0402")
      (description "RES, 10.2 k, 1%, 0.063 W, 0402")
      (fields
        (field (name "VALUEDISPLAYED") "10.2k")
        (field (name "MANUFACTURER") "Vishay-Dale")
        (field (name "PUBLISHER") "Texas Instruments")
      )
      (libsource (lib "Resistor_0402") (part "CRCW040210K2FKED"))
    )
    (comp (ref "R16")
      (value "CRCW040210K2FKED")
      (footprint "0402")
      (description "RES, 10.2 k, 1%, 0.063 W, 0402")
      (fields
        (field (name "VALUEDISPLAYED") "10.2k")
        (field (name "MANUFACTURER") "Vishay-Dale")
        (field (name "PUBLISHER") "Texas Instruments")
      )
      (libsource (lib "Resistor_0402") (part "CRCW040210K2FKED"))
    )
    (comp (ref "R17")
      (value "CRCW060310K5FKEA")
      (footprint "0603")
      (description "RES, 10.5 k, 1%, 0.1 W, 0603")
      (fields
        (field (name "VALUEDISPLAYED") "10.5k")
        (field (name "MANUFACTURER") "Vishay-Dale")
        (field (name "PUBLISHER") "Texas Instruments")
      )
      (libsource (lib "Resistor_0603") (part "CRCW060310K5FKEA"))
    )
    (comp (ref "R18")
      (value "CRCW0402100KDHEDP")
      (footprint "0402")
      (description "RES, 100 k, 0.5%, 0.063 W, 0402")
      (fields
        (field (name "VALUEDISPLAYED") "100k")
        (field (name "MANUFACTURER") "Vishay-Dale")
        (field (name "PUBLISHER") "Texas Instruments")
      )
      (libsource (lib "Resistor_0402") (part "CRCW0402100KDHEDP"))
    )
    (comp (ref "R19")
      (value "CRCW04020000Z0ED")
      (footprint "0402")
      (description "RES, 0, 5%, 0.063 W, 0402")
      (fields
        (field (name "VALUEDISPLAYED") "0")
        (field (name "MANUFACTURER") "Vishay-Dale")
        (field (name "PUBLISHER") "Texas Instruments")
      )
      (libsource (lib "Resistor_0402") (part "CRCW04020000Z0ED"))
    )
    (comp (ref "R20")
      (value "CRCW040212R1FKED")
      (footprint "0402")
      (description "RES, 12.1, 1%, 0.063 W, 0402")
      (fields
        (field (name "VALUEDISPLAYED") "12.1")
        (field (name "MANUFACTURER") "Vishay-Dale")
        (field (name "PUBLISHER") "Texas Instruments")
      )
      (libsource (lib "Resistor_0402") (part "CRCW040212R1FKED"))
    )
    (comp (ref "R21")
      (value "CRCW04020000Z0ED")
      (footprint "0402")
      (description "RES, 0, 5%, 0.063 W, 0402")
      (fields
        (field (name "VALUEDISPLAYED") "0")
        (field (name "MANUFACTURER") "Vishay-Dale")
        (field (name "PUBLISHER") "Texas Instruments")
      )
      (libsource (lib "Resistor_0402") (part "CRCW04020000Z0ED"))
    )
    (comp (ref "R22")
      (value "CRCW0402100KDHEDP")
      (footprint "0402")
      (description "RES, 100 k, 0.5%, 0.063 W, 0402")
      (fields
        (field (name "VALUEDISPLAYED") "100k")
        (field (name "MANUFACTURER") "Vishay-Dale")
        (field (name "PUBLISHER") "Texas Instruments")
      )
      (libsource (lib "Resistor_0402") (part "CRCW0402100KDHEDP"))
    )
    (comp (ref "R23")
      (value "ERJ-2RKF1004X")
      (footprint "0402")
      (description "RES, 1.00 M, 1%, 0.1 W, 0402")
      (fields
        (field (name "VALUEDISPLAYED") "1.00M")
        (field (name "MANUFACTURER") "Panasonic")
        (field (name "PUBLISHER") "Texas Instruments")
      )
      (libsource (lib "Resistor_0402") (part "ERJ-2RKF1004X"))
    )
    (comp (ref "R24")
      (value "CRCW040210K2FKED")
      (footprint "0402")
      (description "RES, 10.2 k, 1%, 0.063 W, 0402")
      (fields
        (field (name "VALUEDISPLAYED") "10.2k")
        (field (name "MANUFACTURER") "Vishay-Dale")
        (field (name "PUBLISHER") "Texas Instruments")
      )
      (libsource (lib "Resistor_0402") (part "CRCW040210K2FKED"))
    )
    (comp (ref "R25")
      (value "CRCW040210K2FKED")
      (footprint "0402")
      (description "RES, 10.2 k, 1%, 0.063 W, 0402")
      (fields
        (field (name "VALUEDISPLAYED") "10.2k")
        (field (name "MANUFACTURER") "Vishay-Dale")
        (field (name "PUBLISHER") "Texas Instruments")
      )
      (libsource (lib "Resistor_0402") (part "CRCW040210K2FKED"))
    )
    (comp (ref "R26")
      (value "CRCW040216K9FKED")
      (footprint "0402")
      (description "RES, 16.9 k, 1%, 0.063 W, 0402")
      (fields
        (field (name "VALUEDISPLAYED") "16.9k")
        (field (name "MANUFACTURER") "Vishay-Dale")
        (field (name "PUBLISHER") "Texas Instruments")
      )
      (libsource (lib "Resistor_0402") (part "CRCW040216K9FKED"))
    )
    (comp (ref "R27")
      (value "CRCW04020000Z0ED")
      (footprint "0402")
      (description "RES, 0, 5%, 0.063 W, 0402")
      (fields
        (field (name "VALUEDISPLAYED") "0")
        (field (name "MANUFACTURER") "Vishay-Dale")
        (field (name "PUBLISHER") "Texas Instruments")
      )
      (libsource (lib "Resistor_0402") (part "CRCW04020000Z0ED"))
    )
    (comp (ref "R28")
      (value "CRCW06033R30JNEA")
      (footprint "0603L")
      (description "RES, 3.3, 5%, 0.1 W, 0603")
      (fields
        (field (name "VALUEDISPLAYED") "3.3")
        (field (name "MANUFACTURER") "Vishay-Dale")
        (field (name "PUBLISHER") "Texas Instruments")
      )
      (libsource (lib "Resistor_0603") (part "CRCW06033R30JNEA"))
    )
    (comp (ref "R29")
      (value "CRCW0402100KDHEDP")
      (footprint "0402")
      (description "RES, 100 k, 0.5%, 0.063 W, 0402")
      (fields
        (field (name "VALUEDISPLAYED") "100k")
        (field (name "MANUFACTURER") "Vishay-Dale")
        (field (name "PUBLISHER") "Texas Instruments")
      )
      (libsource (lib "Resistor_0402") (part "CRCW0402100KDHEDP"))
    )
    (comp (ref "R30")
      (value "CRCW06033R30JNEA")
      (footprint "0603L")
      (description "RES, 3.3, 5%, 0.1 W, 0603")
      (fields
        (field (name "VALUEDISPLAYED") "3.3")
        (field (name "MANUFACTURER") "Vishay-Dale")
        (field (name "PUBLISHER") "Texas Instruments")
      )
      (libsource (lib "Resistor_0603") (part "CRCW06033R30JNEA"))
    )
    (comp (ref "R31")
      (value "RC0603FR-07499KL")
      (footprint "0603L")
      (description "RES, 499 k, 1%, 0.1 W, 0603")
      (fields
        (field (name "MANUFACTURER") "Yageo America")
        (field (name "VALUEDISPLAYED") "499k")
        (field (name "PUBLISHER") "Texas Instruments")
      )
      (libsource (lib "Resistor_0603") (part "RC0603FR-07499KL"))
    )
    (comp (ref "R32")
      (value "CRCW06033R30JNEA")
      (footprint "0603L")
      (description "RES, 3.3, 5%, 0.1 W, 0603")
      (fields
        (field (name "VALUEDISPLAYED") "3.3")
        (field (name "MANUFACTURER") "Vishay-Dale")
        (field (name "PUBLISHER") "Texas Instruments")
      )
      (libsource (lib "Resistor_0603") (part "CRCW06033R30JNEA"))
    )
    (comp (ref "R33")
      (value "ERJ-2GE0R00X")
      (footprint "0402")
      (description "RES, 0, 5%, 0.063 W, 0402")
      (fields
        (field (name "VALUEDISPLAYED") "0")
        (field (name "MANUFACTURER") "Panasonic")
        (field (name "PUBLISHER") "Texas Instruments")
      )
      (libsource (lib "Resistor_0402") (part "ERJ-2GE0R00X"))
    )
    (comp (ref "R34")
      (value "100k")
      (footprint "0603L")
      (description "RES, 100k ohm, 1%, 0.1W, 0603")
      (fields
        (field (name "PARTNUMBER") "RC0603FR-07100KL")
        (field (name "MANUFACTURER") "Yageo America")
        (field (name "PUBLISHER") "Texas Instruments")
      )
      (libsource (lib "Resistor_0603") (part "RC0603FR-07100KL"))
    )
    (comp (ref "R35")
      (value "CRCW040220K5FKED")
      (footprint "0402")
      (description "RES, 20.5 k, 1%, 0.063 W, 0402")
      (fields
        (field (name "VALUEDISPLAYED") "20.5k")
        (field (name "MANUFACTURER") "Vishay-Dale")
        (field (name "PUBLISHER") "Texas Instruments")
      )
      (libsource (lib "Resistor_0402") (part "CRCW040220K5FKED"))
    )
    (comp (ref "R36")
      (value "CRCW040239K0JNED")
      (footprint "0402")
      (description "RES, 39 k, 5%, 0.063 W, 0402")
      (fields
        (field (name "VALUEDISPLAYED") "39k")
        (field (name "MANUFACTURER") "Vishay-Dale")
        (field (name "PUBLISHER") "Texas Instruments")
      )
      (libsource (lib "Resistor_0402") (part "CRCW040239K0JNED"))
    )
    (comp (ref "R37")
      (value "RG1608P-472-B-T5")
      (footprint "0603L")
      (description "RES, 4.70 k, 0.1%, 0.1 W, 0603")
      (fields
        (field (name "VALUEDISPLAYED") "4.70k")
        (field (name "MANUFACTURER") "Susumu Co Ltd")
        (field (name "PUBLISHER") "Texas Instruments")
      )
      (libsource (lib "Resistor_0603") (part "RG1608P-472-B-T5"))
    )
    (comp (ref "R38")
      (value "100k")
      (footprint "0603L")
      (description "RES, 100k ohm, 1%, 0.1W, 0603")
      (fields
        (field (name "PARTNUMBER") "RC0603FR-07100KL")
        (field (name "MANUFACTURER") "Yageo America")
        (field (name "PUBLISHER") "Texas Instruments")
      )
      (libsource (lib "Resistor_0603") (part "RC0603FR-07100KL"))
    )
    (comp (ref "R39")
      (value "100k")
      (footprint "0603L")
      (description "RES, 100k ohm, 1%, 0.1W, 0603")
      (fields
        (field (name "PARTNUMBER") "RC0603FR-07100KL")
        (field (name "MANUFACTURER") "Yageo America")
        (field (name "PUBLISHER") "Texas Instruments")
      )
      (libsource (lib "Resistor_0603") (part "RC0603FR-07100KL"))
    )
    (comp (ref "R40")
      (value "CRCW06033R30JNEA")
      (footprint "0603L")
      (description "RES, 3.3, 5%, 0.1 W, 0603")
      (fields
        (field (name "VALUEDISPLAYED") "3.3")
        (field (name "MANUFACTURER") "Vishay-Dale")
        (field (name "PUBLISHER") "Texas Instruments")
      )
      (libsource (lib "Resistor_0603") (part "CRCW06033R30JNEA"))
    )
    (comp (ref "R41")
      (value "100k")
      (footprint "0603L")
      (description "RES, 100k ohm, 1%, 0.1W, 0603")
      (fields
        (field (name "PARTNUMBER") "RC0603FR-07100KL")
        (field (name "MANUFACTURER") "Yageo America")
        (field (name "PUBLISHER") "Texas Instruments")
      )
      (libsource (lib "Resistor_0603") (part "RC0603FR-07100KL"))
    )
    (comp (ref "R42")
      (value "CRCW080510R0JNEA")
      (footprint "0805_KTR")
      (description "RES, 10, 5%, 0.125 W, 0805")
      (fields
        (field (name "VALUEDISPLAYED") "10")
        (field (name "MANUFACTURER") "Vishay-Dale")
        (field (name "PUBLISHER") "Texas Instruments")
      )
      (libsource (lib "Resistor_0805") (part "CRCW080510R0JNEA"))
    )
    (comp (ref "R43")
      (value "CRCW080510R0JNEA")
      (footprint "0805_KTR")
      (description "RES, 10, 5%, 0.125 W, 0805")
      (fields
        (field (name "VALUEDISPLAYED") "10")
        (field (name "MANUFACTURER") "Vishay-Dale")
        (field (name "PUBLISHER") "Texas Instruments")
      )
      (libsource (lib "Resistor_0805") (part "CRCW080510R0JNEA"))
    )
    (comp (ref "R44")
      (value "CRCW080510R0JNEA")
      (footprint "0805_KTR")
      (description "RES, 10, 5%, 0.125 W, 0805")
      (fields
        (field (name "VALUEDISPLAYED") "10")
        (field (name "MANUFACTURER") "Vishay-Dale")
        (field (name "PUBLISHER") "Texas Instruments")
      )
      (libsource (lib "Resistor_0805") (part "CRCW080510R0JNEA"))
    )
    (comp (ref "R45")
      (value "CRCW080510R0JNEA")
      (footprint "0805_KTR")
      (description "RES, 10, 5%, 0.125 W, 0805")
      (fields
        (field (name "VALUEDISPLAYED") "10")
        (field (name "MANUFACTURER") "Vishay-Dale")
        (field (name "PUBLISHER") "Texas Instruments")
      )
      (libsource (lib "Resistor_0805") (part "CRCW080510R0JNEA"))
    )
    (comp (ref "R46")
      (value "100k")
      (footprint "0603L")
      (description "RES, 100k ohm, 1%, 0.1W, 0603")
      (fields
        (field (name "PARTNUMBER") "RC0603FR-07100KL")
        (field (name "MANUFACTURER") "Yageo America")
        (field (name "PUBLISHER") "Texas Instruments")
      )
      (libsource (lib "Resistor_0603") (part "RC0603FR-07100KL"))
    )
    (comp (ref "Rg1")
      (value "CRCW04020000Z0ED")
      (footprint "0402")
      (description "RES, 0, 5%, 0.063 W, 0402")
      (fields
        (field (name "VALUEDISPLAYED") "0")
        (field (name "MANUFACTURER") "Vishay-Dale")
        (field (name "PUBLISHER") "Texas Instruments")
      )
      (libsource (lib "Resistor_0402") (part "CRCW04020000Z0ED"))
    )
    (comp (ref "Rg2")
      (value "CRCW04020000Z0ED")
      (footprint "0402")
      (description "RES, 0, 5%, 0.063 W, 0402")
      (fields
        (field (name "VALUEDISPLAYED") "0")
        (field (name "MANUFACTURER") "Vishay-Dale")
        (field (name "PUBLISHER") "Texas Instruments")
      )
      (libsource (lib "Resistor_0402") (part "CRCW04020000Z0ED"))
    )
    (comp (ref "TP1")
      (value "R+")
      (footprint "Keystone5003")
      (description "Test Point, Miniature, Orange, TH")
      (fields
        (field (name "PARTNUMBER") "5003")
        (field (name "MANUFACTURER") "Keystone")
        (field (name "PUBLISHER") "Texas Instruments")
      )
      (libsource (lib "Connectors_Keystone") (part "5003"))
    )
    (comp (ref "TP2")
      (value "R-")
      (footprint "Keystone5003")
      (description "Test Point, Miniature, Orange, TH")
      (fields
        (field (name "PARTNUMBER") "5003")
        (field (name "MANUFACTURER") "Keystone")
        (field (name "PUBLISHER") "Texas Instruments")
      )
      (libsource (lib "Connectors_Keystone") (part "5003"))
    )
    (comp (ref "TP3")
      (value "L+")
      (footprint "Keystone5003")
      (description "Test Point, Miniature, Orange, TH")
      (fields
        (field (name "PARTNUMBER") "5003")
        (field (name "MANUFACTURER") "Keystone")
        (field (name "PUBLISHER") "Texas Instruments")
      )
      (libsource (lib "Connectors_Keystone") (part "5003"))
    )
    (comp (ref "TP4")
      (value "PLIMIT")
      (footprint "Keystone5003")
      (description "Test Point, Miniature, Orange, TH")
      (fields
        (field (name "PARTNUMBER") "5003")
        (field (name "MANUFACTURER") "Keystone")
        (field (name "PUBLISHER") "Texas Instruments")
      )
      (libsource (lib "Connectors_Keystone") (part "5003"))
    )
    (comp (ref "TP5")
      (value "L-")
      (footprint "Keystone5003")
      (description "Test Point, Miniature, Orange, TH")
      (fields
        (field (name "PARTNUMBER") "5003")
        (field (name "MANUFACTURER") "Keystone")
        (field (name "PUBLISHER") "Texas Instruments")
      )
      (libsource (lib "Connectors_Keystone") (part "5003"))
    )
    (comp (ref "U1")
      (value "TPS613222ADBVR")
      (footprint "DBV0005A_N")
      (description "6.5-μA Quiescent Current, 1.8-A Switch Current Boost Converter, DBV0005A (SOT-23-5)")
      (fields
        (field (name "ALTERNATE PARTNUMBER") "TPS613222ADBVT")
        (field (name "MANUFACTURER") "Texas Instruments")
        (field (name "PARTNUMBER") "TPS613222ADBVR")
      )
      (libsource (lib "Altium Vault - TI") (part "CMP-0079087-1"))
    )
    (comp (ref "U2")
      (value "TPS43061RTER")
      (footprint "RTE0016E")
      (fields
        (field (name "ALTERNATE PARTNUMBER") "TPS43061RTET")
        (field (name "MANUFACTURER") "Texas Instruments")
        (field (name "PARTNUMBER") "TPS43061RTER")
        (field (name "PUBLISHER") "Texas Instruments")
      )
      (libsource (lib "Altium Vault - TI") (part "TPS43061"))
    )
    (comp (ref "U3")
      (value "OPA4377AIPW")
      (footprint "PW0014A_N")
      (fields
        (field (name "MANUFACTURER") "Texas Instruments")
        (field (name "ALTERNATE PARTNUMBER") "Equivalent")
      )
      (libsource (lib "TI Amplifiers and Linear Operational Amplifier Precision Amplifier Part One") (part "OPA4377AIPW"))
    )
    (comp (ref "U4")
      (value "TPA3128D2DAPR")
      (footprint "DAP0032A_N")
      (description "2x30-W Class-D Amplifier With Low Idle Power Dissipation, DAP0032A (TSSOP-32)")
      (fields
        (field (name "ALTERNATE PARTNUMBER") "TPA3128D2DAP")
        (field (name "MANUFACTURER") "Texas Instruments")
        (field (name "SYMBOLCREATOR") "Altium")
        (field (name "PUBLISHER") "Texas Instruments")
      )
      (libsource (lib "TI_Pre_Release1") (part "TPA3128D2DAPR"))
    )
  )
  (nets
    (net (code "1") (name "/AVCC") (class "Default")
      (node (ref "C31") (pin "1") (pinfunction "1_1") (pintype "passive"))
      (node (ref "J9") (pin "2") (pinfunction "2_2") (pintype "passive"))
      (node (ref "U4") (pin "17") (pinfunction "AVCC_17") (pintype "power_in"))
    )
    (net (code "2") (name "/AVCC-IN") (class "Default")
      (node (ref "C29") (pin "1") (pinfunction "1_1") (pintype "passive"))
      (node (ref "J11") (pin "1") (pintype "passive"))
      (node (ref "J9") (pin "1") (pinfunction "1_1") (pintype "passive"))
    )
    (net (code "3") (name "/Boot") (class "Default")
      (node (ref "C11") (pin "2") (pinfunction "2_2") (pintype "passive"))
      (node (ref "U2") (pin "11") (pinfunction "BOOT_11") (pintype "passive"))
    )
    (net (code "4") (name "/COMP") (class "Default")
      (node (ref "C15") (pin "1") (pinfunction "1_1") (pintype "passive"))
      (node (ref "R12") (pin "2") (pinfunction "2_2") (pintype "passive"))
      (node (ref "U2") (pin "3") (pinfunction "COMP_3") (pintype "output"))
    )
    (net (code "5") (name "/EN") (class "Default")
      (node (ref "J6") (pin "2") (pinfunction "2_2") (pintype "passive"))
      (node (ref "R7") (pin "2") (pinfunction "2_2") (pintype "passive"))
    )
    (net (code "6") (name "/EN1") (class "Default")
      (node (ref "C14") (pin "1") (pinfunction "1_1") (pintype "passive"))
      (node (ref "R7") (pin "1") (pinfunction "1_1") (pintype "passive"))
      (node (ref "U2") (pin "15") (pinfunction "EN_15") (pintype "input"))
    )
    (net (code "7") (name "/FAULT") (class "Default")
      (node (ref "R41") (pin "2") (pinfunction "2_2") (pintype "passive"))
      (node (ref "R46") (pin "1") (pinfunction "1_1") (pintype "passive"))
      (node (ref "U4") (pin "3") (pinfunction "FAULTZ_3") (pintype "output"))
    )
    (net (code "8") (name "/FB") (class "Default")
      (node (ref "C20") (pin "1") (pinfunction "1_1") (pintype "passive"))
      (node (ref "R10") (pin "2") (pinfunction "2_2") (pintype "passive"))
      (node (ref "R17") (pin "2") (pinfunction "2_2") (pintype "passive"))
      (node (ref "R6") (pin "1") (pinfunction "1_1") (pintype "passive"))
      (node (ref "U2") (pin "4") (pinfunction "FB_4") (pintype "input"))
    )
    (net (code "9") (name "/GVDD") (class "Default")
      (node (ref "C47") (pin "2") (pinfunction "2_2") (pintype "passive"))
      (node (ref "R33") (pin "2") (pinfunction "2_2") (pintype "passive"))
      (node (ref "R34") (pin "1") (pinfunction "1_1") (pintype "passive"))
      (node (ref "U4") (pin "7") (pinfunction "GVDD_7") (pintype "passive"))
    )
    (net (code "10") (name "/HDRV") (class "Default")
      (node (ref "R11") (pin "1") (pinfunction "1_1") (pintype "passive"))
      (node (ref "U2") (pin "13") (pinfunction "HDRV_13") (pintype "power_in"))
    )
    (net (code "11") (name "/HDRV1") (class "Default")
      (node (ref "Q1") (pin "3") (pinfunction "TG_3") (pintype "passive"))
      (node (ref "R11") (pin "2") (pinfunction "2_2") (pintype "passive"))
    )
    (net (code "12") (name "/ISNS+") (class "Default")
      (node (ref "C6") (pin "2") (pinfunction "2_2") (pintype "passive"))
      (node (ref "R2") (pin "1") (pinfunction "1_1") (pintype "passive"))
      (node (ref "U2") (pin "6") (pinfunction "ISNS+_6") (pintype "input"))
    )
    (net (code "13") (name "/ISNS-") (class "Default")
      (node (ref "C6") (pin "1") (pinfunction "1_1") (pintype "passive"))
      (node (ref "R3") (pin "1") (pinfunction "1_1") (pintype "passive"))
      (node (ref "U2") (pin "5") (pinfunction "ISNS-_5") (pintype "input"))
    )
    (net (code "14") (name "/LDRV") (class "Default")
      (node (ref "R9") (pin "1") (pinfunction "1_1") (pintype "passive"))
      (node (ref "U2") (pin "8") (pinfunction "LDRV_8") (pintype "power_in"))
    )
    (net (code "15") (name "/LDRV1") (class "Default")
      (node (ref "Q1") (pin "5") (pinfunction "BG_5") (pintype "passive"))
      (node (ref "R9") (pin "2") (pinfunction "2_2") (pintype "passive"))
    )
    (net (code "16") (name "/LIN") (class "Default")
      (node (ref "C23") (pin "1") (pinfunction "1_1") (pintype "passive"))
      (node (ref "C42") (pin "1") (pinfunction "1_1") (pintype "passive"))
      (node (ref "J10") (pin "1") (pinfunction "1_1") (pintype "passive"))
      (node (ref "J15") (pin "3") (pinfunction "TIP_3") (pintype "passive"))
    )
    (net (code "17") (name "/LINN") (class "Default")
      (node (ref "C45") (pin "2") (pinfunction "2_2") (pintype "passive"))
      (node (ref "U4") (pin "11") (pinfunction "LINN_11") (pintype "input"))
    )
    (net (code "18") (name "/LINP") (class "Default")
      (node (ref "C42") (pin "2") (pinfunction "2_2") (pintype "passive"))
      (node (ref "U4") (pin "10") (pinfunction "LINP_10") (pintype "input"))
    )
    (net (code "19") (name "/MODSEL") (class "Default")
      (node (ref "J17") (pin "2") (pinfunction "2_2") (pintype "passive"))
      (node (ref "U4") (pin "1") (pinfunction "MODSEL_1") (pintype "input"))
    )
    (net (code "20") (name "/MUTE") (class "Default")
      (node (ref "Q4") (pin "3") (pinfunction "C_3") (pintype "passive"))
      (node (ref "R38") (pin "2") (pinfunction "2_2") (pintype "passive"))
      (node (ref "U4") (pin "12") (pinfunction "MUTE_12") (pintype "input"))
    )
    (net (code "21") (name "/OUTL+") (class "Default")
      (node (ref "C43") (pin "1") (pinfunction "1_1") (pintype "passive"))
      (node (ref "C44") (pin "1") (pinfunction "1_1") (pintype "passive"))
      (node (ref "J14") (pin "1") (pinfunction "1_1") (pintype "passive"))
      (node (ref "L5") (pin "2") (pinfunction "2_2") (pintype "passive"))
      (node (ref "TP3") (pin "1") (pintype "passive"))
    )
    (net (code "22") (name "/OUTL-") (class "Default")
      (node (ref "C48") (pin "1") (pinfunction "1_1") (pintype "passive"))
      (node (ref "C49") (pin "1") (pinfunction "1_1") (pintype "passive"))
      (node (ref "J16") (pin "1") (pinfunction "1_1") (pintype "passive"))
      (node (ref "L6") (pin "2") (pinfunction "2_2") (pintype "passive"))
      (node (ref "TP5") (pin "1") (pintype "passive"))
    )
    (net (code "23") (name "/OUTNL") (class "Default")
      (node (ref "C41") (pin "1") (pinfunction "1_1") (pintype "passive"))
      (node (ref "C54") (pin "2") (pinfunction "2_2") (pintype "passive"))
      (node (ref "L6") (pin "1") (pinfunction "1_1") (pintype "passive"))
      (node (ref "U4") (pin "21") (pinfunction "OUTNL_21") (pintype "tri_state"))
    )
    (net (code "24") (name "/OUTNR") (class "Default")
      (node (ref "C38") (pin "1") (pinfunction "1_1") (pintype "passive"))
      (node (ref "C52") (pin "2") (pinfunction "2_2") (pintype "passive"))
      (node (ref "L4") (pin "1") (pinfunction "1_1") (pintype "passive"))
      (node (ref "U4") (pin "27") (pinfunction "OUTNR_27") (pintype "tri_state"))
    )
    (net (code "25") (name "/OUTPL") (class "Default")
      (node (ref "C40") (pin "1") (pinfunction "1_1") (pintype "passive"))
      (node (ref "C53") (pin "2") (pinfunction "2_2") (pintype "passive"))
      (node (ref "L5") (pin "1") (pinfunction "1_1") (pintype "passive"))
      (node (ref "U4") (pin "23") (pinfunction "OUTPL_23") (pintype "tri_state"))
    )
    (net (code "26") (name "/OUTPR") (class "Default")
      (node (ref "C39") (pin "1") (pinfunction "1_1") (pintype "passive"))
      (node (ref "C51") (pin "2") (pinfunction "2_2") (pintype "passive"))
      (node (ref "L3") (pin "1") (pinfunction "1_1") (pintype "passive"))
      (node (ref "U4") (pin "29") (pinfunction "OUTPR_29") (pintype "tri_state"))
    )
    (net (code "27") (name "/OUTR+") (class "Default")
      (node (ref "C24") (pin "1") (pinfunction "1_1") (pintype "passive"))
      (node (ref "C25") (pin "1") (pinfunction "1_1") (pintype "passive"))
      (node (ref "J8") (pin "1") (pinfunction "1_1") (pintype "passive"))
      (node (ref "L3") (pin "2") (pinfunction "2_2") (pintype "passive"))
      (node (ref "TP1") (pin "1") (pintype "passive"))
    )
    (net (code "28") (name "/OUTR-") (class "Default")
      (node (ref "C36") (pin "1") (pinfunction "1_1") (pintype "passive"))
      (node (ref "C37") (pin "1") (pinfunction "1_1") (pintype "passive"))
      (node (ref "J13") (pin "1") (pinfunction "1_1") (pintype "passive"))
      (node (ref "L4") (pin "2") (pinfunction "2_2") (pintype "passive"))
      (node (ref "TP2") (pin "1") (pintype "passive"))
    )
    (net (code "29") (name "/PGOOD") (class "Default")
      (node (ref "R8") (pin "2") (pinfunction "2_2") (pintype "passive"))
      (node (ref "U2") (pin "14") (pinfunction "PGOOD_14") (pintype "output"))
    )
    (net (code "30") (name "/PLIMIT") (class "Default")
      (node (ref "C46") (pin "2") (pinfunction "2_2") (pintype "passive"))
      (node (ref "R33") (pin "1") (pinfunction "1_1") (pintype "passive"))
      (node (ref "R35") (pin "2") (pinfunction "2_2") (pintype "passive"))
      (node (ref "TP4") (pin "1") (pintype "passive"))
      (node (ref "U4") (pin "6") (pinfunction "PLIMIT_6") (pintype "input"))
    )
    (net (code "31") (name "/RIN") (class "Default")
      (node (ref "C21") (pin "1") (pinfunction "1_1") (pintype "passive"))
      (node (ref "C30") (pin "1") (pinfunction "1_1") (pintype "passive"))
      (node (ref "J12") (pin "3") (pinfunction "TIP_3") (pintype "passive"))
      (node (ref "J7") (pin "1") (pinfunction "1_1") (pintype "passive"))
    )
    (net (code "32") (name "/RINN") (class "Default")
      (node (ref "C35") (pin "2") (pinfunction "2_2") (pintype "passive"))
      (node (ref "U4") (pin "5") (pinfunction "RINN_5") (pintype "input"))
    )
    (net (code "33") (name "/RINP") (class "Default")
      (node (ref "C30") (pin "2") (pinfunction "2_2") (pintype "passive"))
      (node (ref "U4") (pin "4") (pinfunction "RINP_4") (pintype "input"))
    )
    (net (code "34") (name "/SD") (class "Default")
      (node (ref "R31") (pin "1") (pinfunction "1_1") (pintype "passive"))
      (node (ref "U4") (pin "2") (pinfunction "SDZ_2") (pintype "input"))
    )
    (net (code "35") (name "/SW") (class "Default")
      (node (ref "L2") (pin "2") (pinfunction "2_2") (pintype "passive"))
      (node (ref "Q1") (pin "6") (pinfunction "VSW_6") (pintype "passive"))
      (node (ref "Q1") (pin "7") (pinfunction "VSW_7") (pintype "passive"))
      (node (ref "Q1") (pin "8") (pinfunction "VSW_8") (pintype "passive"))
    )
    (net (code "36") (name "/SW1") (class "Default")
      (node (ref "C11") (pin "1") (pinfunction "1_1") (pintype "passive"))
      (node (ref "Q1") (pin "4") (pinfunction "TGR_4") (pintype "passive"))
      (node (ref "U2") (pin "12") (pinfunction "SW_12") (pintype "power_in"))
    )
    (net (code "37") (name "/V+") (class "Default")
      (node (ref "C18") (pin "1") (pinfunction "1_1") (pintype "passive"))
      (node (ref "C19") (pin "1") (pinfunction "1_1") (pintype "passive"))
      (node (ref "Q2") (pin "2") (pinfunction "E_2") (pintype "passive"))
      (node (ref "U3") (pin "4") (pinfunction "V+_4") (pintype "power_in"))
    )
    (net (code "38") (name "/Vin_ctrl") (class "Default")
      (node (ref "J4") (pin "2") (pinfunction "2_2") (pintype "passive"))
      (node (ref "J6") (pin "3") (pinfunction "3_3") (pintype "passive"))
      (node (ref "Q2") (pin "3") (pinfunction "C_3") (pintype "passive"))
      (node (ref "R14") (pin "2") (pinfunction "2_2") (pintype "passive"))
      (node (ref "R5") (pin "2") (pinfunction "2_2") (pintype "passive"))
    )
    (net (code "39") (name "/Vin_one cell") (class "Default")
      (node (ref "C1") (pin "1") (pinfunction "1_1") (pintype "passive"))
      (node (ref "JP1") (pin "1") (pinfunction "1_1") (pintype "passive"))
      (node (ref "L1") (pin "1") (pinfunction "1_1") (pintype "passive"))
    )
    (net (code "41") (name "5V") (class "Default")
      (node (ref "C2") (pin "1") (pinfunction "1_1") (pintype "passive"))
      (node (ref "J4") (pin "1") (pinfunction "1_1") (pintype "passive"))
      (node (ref "U1") (pin "4") (pinfunction "VOUT_4") (pintype "power_in"))
      (node (ref "U1") (pin "5") (pinfunction "NC_5") (pintype "passive"))
    )
    (net (code "42") (name "AGND") (class "Default")
      (node (ref "C1") (pin "2") (pinfunction "2_2") (pintype "passive"))
      (node (ref "C13") (pin "2") (pinfunction "2_2") (pintype "passive"))
      (node (ref "C14") (pin "2") (pinfunction "2_2") (pintype "passive"))
      (node (ref "C15") (pin "2") (pinfunction "2_2") (pintype "passive"))
      (node (ref "C16") (pin "2") (pinfunction "2_2") (pintype "passive"))
      (node (ref "C17") (pin "2") (pinfunction "2_2") (pintype "passive"))
      (node (ref "C18") (pin "2") (pinfunction "2_2") (pintype "passive"))
      (node (ref "C19") (pin "2") (pinfunction "2_2") (pintype "passive"))
      (node (ref "C2") (pin "2") (pinfunction "2_2") (pintype "passive"))
      (node (ref "C20") (pin "2") (pinfunction "2_2") (pintype "passive"))
      (node (ref "C22") (pin "2") (pinfunction "2_2") (pintype "passive"))
      (node (ref "D1") (pin "1") (pinfunction "A_1") (pintype "passive"))
      (node (ref "J10") (pin "2") (pinfunction "2_2") (pintype "passive"))
      (node (ref "J6") (pin "1") (pinfunction "1_1") (pintype "passive"))
      (node (ref "J7") (pin "2") (pinfunction "2_2") (pintype "passive"))
      (node (ref "R10") (pin "1") (pinfunction "1_1") (pintype "passive"))
      (node (ref "R13") (pin "1") (pinfunction "1_1") (pintype "passive"))
      (node (ref "R15") (pin "1") (pinfunction "1_1") (pintype "passive"))
      (node (ref "R18") (pin "1") (pinfunction "1_1") (pintype "passive"))
      (node (ref "R22") (pin "1") (pinfunction "1_1") (pintype "passive"))
      (node (ref "R23") (pin "1") (pinfunction "1_1") (pintype "passive"))
      (node (ref "R24") (pin "1") (pinfunction "1_1") (pintype "passive"))
      (node (ref "R26") (pin "1") (pinfunction "1_1") (pintype "passive"))
      (node (ref "R29") (pin "1") (pinfunction "1_1") (pintype "passive"))
      (node (ref "Rg1") (pin "1") (pinfunction "1_1") (pintype "passive"))
      (node (ref "Rg2") (pin "1") (pinfunction "1_1") (pintype "passive"))
      (node (ref "U1") (pin "2") (pinfunction "GND_2") (pintype "power_in"))
      (node (ref "U1") (pin "3") (pinfunction "NC_3") (pintype "passive"))
      (node (ref "U2") (pin "16") (pinfunction "AGND_16") (pintype "power_in"))
      (node (ref "U2") (pin "17") (pinfunction "PAD_17") (pintype "power_in"))
      (node (ref "U3") (pin "11") (pinfunction "V-_11") (pintype "power_in"))
    )
    (net (code "43") (name "GND") (class "Default")
      (node (ref "C10") (pin "2") (pinfunction "2_2") (pintype "passive"))
      (node (ref "C12") (pin "2") (pinfunction "2_2") (pintype "passive"))
      (node (ref "C24") (pin "2") (pinfunction "2_2") (pintype "passive"))
      (node (ref "C26") (pin "2") (pinfunction "-_2") (pintype "passive"))
      (node (ref "C27") (pin "1") (pinfunction "1_1") (pintype "passive"))
      (node (ref "C28") (pin "1") (pinfunction "1_1") (pintype "passive"))
      (node (ref "C29") (pin "2") (pinfunction "2_2") (pintype "passive"))
      (node (ref "C3") (pin "2") (pinfunction "-_2") (pintype "passive"))
      (node (ref "C31") (pin "2") (pinfunction "2_2") (pintype "passive"))
      (node (ref "C32") (pin "2") (pinfunction "-_2") (pintype "passive"))
      (node (ref "C33") (pin "1") (pinfunction "1_1") (pintype "passive"))
      (node (ref "C34") (pin "1") (pinfunction "1_1") (pintype "passive"))
      (node (ref "C36") (pin "2") (pinfunction "2_2") (pintype "passive"))
      (node (ref "C4") (pin "2") (pinfunction "2_2") (pintype "passive"))
      (node (ref "C43") (pin "2") (pinfunction "2_2") (pintype "passive"))
      (node (ref "C46") (pin "1") (pinfunction "1_1") (pintype "passive"))
      (node (ref "C47") (pin "1") (pinfunction "1_1") (pintype "passive"))
      (node (ref "C48") (pin "2") (pinfunction "2_2") (pintype "passive"))
      (node (ref "C5") (pin "2") (pinfunction "2_2") (pintype "passive"))
      (node (ref "C50") (pin "2") (pinfunction "2_2") (pintype "passive"))
      (node (ref "C7") (pin "2") (pinfunction "2_2") (pintype "passive"))
      (node (ref "C8") (pin "2") (pinfunction "2_2") (pintype "passive"))
      (node (ref "C9") (pin "2") (pinfunction "2_2") (pintype "passive"))
      (node (ref "H1") (pin "1") (pintype "passive"))
      (node (ref "H1") (pin "2") (pintype "passive"))
      (node (ref "J17") (pin "3") (pinfunction "3_3") (pintype "passive"))
      (node (ref "J2") (pin "1") (pintype "passive"))
      (node (ref "J5") (pin "1") (pintype "passive"))
      (node (ref "JP2") (pin "2") (pinfunction "2_2") (pintype "passive"))
      (node (ref "JP3") (pin "2") (pinfunction "2_2") (pintype "passive"))
      (node (ref "Q1") (pin "9") (pinfunction "PGND_9") (pintype "passive"))
      (node (ref "Q4") (pin "2") (pinfunction "E_2") (pintype "passive"))
      (node (ref "R28") (pin "1") (pinfunction "1_1") (pintype "passive"))
      (node (ref "R30") (pin "1") (pinfunction "1_1") (pintype "passive"))
      (node (ref "R32") (pin "1") (pinfunction "1_1") (pintype "passive"))
      (node (ref "R35") (pin "1") (pinfunction "1_1") (pintype "passive"))
      (node (ref "R36") (pin "1") (pinfunction "1_1") (pintype "passive"))
      (node (ref "R40") (pin "1") (pinfunction "1_1") (pintype "passive"))
      (node (ref "R42") (pin "1") (pinfunction "1_1") (pintype "passive"))
      (node (ref "R43") (pin "1") (pinfunction "1_1") (pintype "passive"))
      (node (ref "R44") (pin "1") (pinfunction "1_1") (pintype "passive"))
      (node (ref "R45") (pin "1") (pinfunction "1_1") (pintype "passive"))
      (node (ref "Rg1") (pin "2") (pinfunction "2_2") (pintype "passive"))
      (node (ref "Rg2") (pin "2") (pinfunction "2_2") (pintype "passive"))
      (node (ref "U2") (pin "9") (pinfunction "PGND_9") (pintype "power_in"))
      (node (ref "U4") (pin "13") (pinfunction "AM2_13") (pintype "input"))
      (node (ref "U4") (pin "14") (pinfunction "AM1_14") (pintype "input"))
      (node (ref "U4") (pin "15") (pinfunction "AM0_15") (pintype "input"))
      (node (ref "U4") (pin "22") (pinfunction "GND_22") (pintype "power_in"))
      (node (ref "U4") (pin "25") (pinfunction "GND_25") (pintype "power_in"))
      (node (ref "U4") (pin "28") (pinfunction "GND_28") (pintype "power_in"))
      (node (ref "U4") (pin "33") (pinfunction "PAD_33") (pintype "power_in"))
      (node (ref "U4") (pin "9") (pinfunction "GND_9") (pintype "power_in"))
    )
    (net (code "44") (name "Net-(C17-Pad1)") (class "Default")
      (node (ref "C17") (pin "1") (pinfunction "1_1") (pintype "passive"))
      (node (ref "R12") (pin "1") (pinfunction "1_1") (pintype "passive"))
    )
    (net (code "45") (name "Net-(C21-Pad2)") (class "Default")
      (node (ref "C21") (pin "2") (pinfunction "2_2") (pintype "passive"))
      (node (ref "R19") (pin "2") (pinfunction "2_2") (pintype "passive"))
    )
    (net (code "46") (name "Net-(C23-Pad2)") (class "Default")
      (node (ref "C23") (pin "2") (pinfunction "2_2") (pintype "passive"))
      (node (ref "R27") (pin "2") (pinfunction "2_2") (pintype "passive"))
    )
    (net (code "47") (name "Net-(C25-Pad2)") (class "Default")
      (node (ref "C25") (pin "2") (pinfunction "2_2") (pintype "passive"))
      (node (ref "R28") (pin "2") (pinfunction "2_2") (pintype "passive"))
    )
    (net (code "48") (name "Net-(C37-Pad2)") (class "Default")
      (node (ref "C37") (pin "2") (pinfunction "2_2") (pintype "passive"))
      (node (ref "R30") (pin "2") (pinfunction "2_2") (pintype "passive"))
    )
    (net (code "49") (name "Net-(C44-Pad2)") (class "Default")
      (node (ref "C44") (pin "2") (pinfunction "2_2") (pintype "passive"))
      (node (ref "R32") (pin "2") (pinfunction "2_2") (pintype "passive"))
    )
    (net (code "50") (name "Net-(C49-Pad2)") (class "Default")
      (node (ref "C49") (pin "2") (pinfunction "2_2") (pintype "passive"))
      (node (ref "R40") (pin "2") (pinfunction "2_2") (pintype "passive"))
    )
    (net (code "51") (name "Net-(C50-Pad1)") (class "Default")
      (node (ref "C50") (pin "1") (pinfunction "1_1") (pintype "passive"))
      (node (ref "R37") (pin "1") (pinfunction "1_1") (pintype "passive"))
    )
    (net (code "52") (name "Net-(C51-Pad1)") (class "Default")
      (node (ref "C51") (pin "1") (pinfunction "1_1") (pintype "passive"))
      (node (ref "R42") (pin "2") (pinfunction "2_2") (pintype "passive"))
    )
    (net (code "53") (name "Net-(C52-Pad1)") (class "Default")
      (node (ref "C52") (pin "1") (pinfunction "1_1") (pintype "passive"))
      (node (ref "R43") (pin "2") (pinfunction "2_2") (pintype "passive"))
    )
    (net (code "54") (name "Net-(C53-Pad1)") (class "Default")
      (node (ref "C53") (pin "1") (pinfunction "1_1") (pintype "passive"))
      (node (ref "R44") (pin "2") (pinfunction "2_2") (pintype "passive"))
    )
    (net (code "55") (name "Net-(C54-Pad1)") (class "Default")
      (node (ref "C54") (pin "1") (pinfunction "1_1") (pintype "passive"))
      (node (ref "R45") (pin "2") (pinfunction "2_2") (pintype "passive"))
    )
    (net (code "56") (name "Net-(D1-K)") (class "Default")
      (node (ref "D1") (pin "3") (pinfunction "K_3") (pintype "passive"))
      (node (ref "Q2") (pin "1") (pinfunction "B_1") (pintype "passive"))
      (node (ref "R14") (pin "1") (pinfunction "1_1") (pintype "passive"))
    )
    (net (code "57") (name "Net-(D2-A)") (class "Default")
      (node (ref "D2") (pin "2") (pinfunction "A_2") (pintype "passive"))
      (node (ref "U3") (pin "1") (pinfunction "OUT_A_1") (pintype "output"))
    )
    (net (code "58") (name "Net-(D2-K)") (class "Default")
      (node (ref "D2") (pin "1") (pinfunction "K_1") (pintype "passive"))
      (node (ref "D4") (pin "1") (pinfunction "K_1") (pintype "passive"))
      (node (ref "R16") (pin "2") (pinfunction "2_2") (pintype "passive"))
      (node (ref "R18") (pin "2") (pinfunction "2_2") (pintype "passive"))
      (node (ref "R25") (pin "2") (pinfunction "2_2") (pintype "passive"))
      (node (ref "U3") (pin "12") (pinfunction "IN_D+_12") (pintype "input"))
    )
    (net (code "59") (name "Net-(D3-A)") (class "Default")
      (node (ref "D3") (pin "2") (pinfunction "A_2") (pintype "passive"))
      (node (ref "U3") (pin "14") (pinfunction "OUT_D_14") (pintype "output"))
    )
    (net (code "60") (name "Net-(D3-K)") (class "Default")
      (node (ref "D3") (pin "1") (pinfunction "K_1") (pintype "passive"))
      (node (ref "R20") (pin "1") (pinfunction "1_1") (pintype "passive"))
      (node (ref "U3") (pin "13") (pinfunction "IN_D-_13") (pintype "input"))
    )
    (net (code "61") (name "Net-(D4-A)") (class "Default")
      (node (ref "D4") (pin "2") (pinfunction "A_2") (pintype "passive"))
      (node (ref "U3") (pin "7") (pinfunction "OUT_B_7") (pintype "output"))
    )
    (net (code "62") (name "Net-(J12-SLEEVE)") (class "Default")
      (node (ref "C35") (pin "1") (pinfunction "1_1") (pintype "passive"))
      (node (ref "J12") (pin "1") (pinfunction "SLEEVE_1") (pintype "passive"))
      (node (ref "J12") (pin "4") (pinfunction "TIP_SWITCH_4") (pintype "passive"))
      (node (ref "JP2") (pin "1") (pinfunction "1_1") (pintype "passive"))
    )
    (net (code "63") (name "Net-(J15-SLEEVE)") (class "Default")
      (node (ref "C45") (pin "1") (pinfunction "1_1") (pintype "passive"))
      (node (ref "J15") (pin "1") (pinfunction "SLEEVE_1") (pintype "passive"))
      (node (ref "J15") (pin "4") (pinfunction "TIP_SWITCH_4") (pintype "passive"))
      (node (ref "JP3") (pin "1") (pinfunction "1_1") (pintype "passive"))
    )
    (net (code "64") (name "Net-(J17-Pad1)") (class "Default")
      (node (ref "J17") (pin "1") (pinfunction "1_1") (pintype "passive"))
      (node (ref "R39") (pin "1") (pinfunction "1_1") (pintype "passive"))
    )
    (net (code "65") (name "Net-(L2-Pad1)") (class "Default")
      (node (ref "L2") (pin "1") (pinfunction "1_1") (pintype "passive"))
      (node (ref "R1") (pin "2") (pinfunction "2_2") (pintype "passive"))
      (node (ref "R3") (pin "2") (pinfunction "2_2") (pintype "passive"))
    )
    (net (code "66") (name "Net-(Q3-D)") (class "Default")
      (node (ref "Q3") (pin "3") (pinfunction "D_3") (pintype "passive"))
      (node (ref "R17") (pin "1") (pinfunction "1_1") (pintype "passive"))
    )
    (net (code "67") (name "Net-(Q3-G)") (class "Default")
      (node (ref "Q3") (pin "1") (pinfunction "G_1") (pintype "passive"))
      (node (ref "R21") (pin "1") (pinfunction "1_1") (pintype "passive"))
    )
    (net (code "68") (name "Net-(Q3-S)") (class "Default")
      (node (ref "Q3") (pin "2") (pinfunction "S_2") (pintype "passive"))
      (node (ref "R26") (pin "2") (pinfunction "2_2") (pintype "passive"))
      (node (ref "U3") (pin "9") (pinfunction "IN_C-_9") (pintype "input"))
    )
    (net (code "69") (name "Net-(Q4-B)") (class "Default")
      (node (ref "Q4") (pin "1") (pinfunction "B_1") (pintype "passive"))
      (node (ref "R46") (pin "2") (pinfunction "2_2") (pintype "passive"))
    )
    (net (code "70") (name "Net-(R4-Pad1)") (class "Default")
      (node (ref "R4") (pin "1") (pinfunction "1_1") (pintype "passive"))
      (node (ref "R6") (pin "2") (pinfunction "2_2") (pintype "passive"))
    )
    (net (code "71") (name "Net-(U1-SW)") (class "Default")
      (node (ref "L1") (pin "2") (pinfunction "2_2") (pintype "passive"))
      (node (ref "U1") (pin "1") (pinfunction "SW_1") (pintype "power_in"))
    )
    (net (code "72") (name "Net-(U2-RT{slash}CLK)") (class "Default")
      (node (ref "R13") (pin "2") (pinfunction "2_2") (pintype "passive"))
      (node (ref "U2") (pin "1") (pinfunction "RT/CLK_1") (pintype "input"))
    )
    (net (code "73") (name "Net-(U2-SS)") (class "Default")
      (node (ref "C16") (pin "1") (pinfunction "1_1") (pintype "passive"))
      (node (ref "U2") (pin "2") (pinfunction "SS_2") (pintype "input"))
    )
    (net (code "74") (name "Net-(U2-VIN)") (class "Default")
      (node (ref "C13") (pin "1") (pinfunction "1_1") (pintype "passive"))
      (node (ref "R5") (pin "1") (pinfunction "1_1") (pintype "passive"))
      (node (ref "U2") (pin "7") (pinfunction "VIN_7") (pintype "power_in"))
    )
    (net (code "75") (name "Net-(U3A-IN_A+)") (class "Default")
      (node (ref "R19") (pin "1") (pinfunction "1_1") (pintype "passive"))
      (node (ref "R22") (pin "2") (pinfunction "2_2") (pintype "passive"))
      (node (ref "U3") (pin "3") (pinfunction "IN_A+_3") (pintype "input"))
    )
    (net (code "76") (name "Net-(U3A-IN_A-)") (class "Default")
      (node (ref "R15") (pin "2") (pinfunction "2_2") (pintype "passive"))
      (node (ref "R16") (pin "1") (pinfunction "1_1") (pintype "passive"))
      (node (ref "U3") (pin "2") (pinfunction "IN_A-_2") (pintype "input"))
    )
    (net (code "77") (name "Net-(U3B-IN_B+)") (class "Default")
      (node (ref "R27") (pin "1") (pinfunction "1_1") (pintype "passive"))
      (node (ref "R29") (pin "2") (pinfunction "2_2") (pintype "passive"))
      (node (ref "U3") (pin "5") (pinfunction "IN_B+_5") (pintype "input"))
    )
    (net (code "78") (name "Net-(U3B-IN_B-)") (class "Default")
      (node (ref "R24") (pin "2") (pinfunction "2_2") (pintype "passive"))
      (node (ref "R25") (pin "1") (pinfunction "1_1") (pintype "passive"))
      (node (ref "U3") (pin "6") (pinfunction "IN_B-_6") (pintype "input"))
    )
    (net (code "79") (name "Net-(U3C-IN_C+)") (class "Default")
      (node (ref "C22") (pin "1") (pinfunction "1_1") (pintype "passive"))
      (node (ref "R20") (pin "2") (pinfunction "2_2") (pintype "passive"))
      (node (ref "R23") (pin "2") (pinfunction "2_2") (pintype "passive"))
      (node (ref "U3") (pin "10") (pinfunction "IN_C+_10") (pintype "input"))
    )
    (net (code "80") (name "Net-(U3C-OUT_C)") (class "Default")
      (node (ref "R21") (pin "2") (pinfunction "2_2") (pintype "passive"))
      (node (ref "U3") (pin "8") (pinfunction "OUT_C_8") (pintype "output"))
    )
    (net (code "81") (name "Net-(U4-BSNL)") (class "Default")
      (node (ref "C41") (pin "2") (pinfunction "2_2") (pintype "passive"))
      (node (ref "U4") (pin "20") (pinfunction "BSNL_20") (pintype "passive"))
    )
    (net (code "82") (name "Net-(U4-BSNR)") (class "Default")
      (node (ref "C38") (pin "2") (pinfunction "2_2") (pintype "passive"))
      (node (ref "U4") (pin "26") (pinfunction "BSNR_26") (pintype "passive"))
    )
    (net (code "83") (name "Net-(U4-BSPL)") (class "Default")
      (node (ref "C40") (pin "2") (pinfunction "2_2") (pintype "passive"))
      (node (ref "U4") (pin "24") (pinfunction "BSPL_24") (pintype "passive"))
    )
    (net (code "84") (name "Net-(U4-BSPR)") (class "Default")
      (node (ref "C39") (pin "2") (pinfunction "2_2") (pintype "passive"))
      (node (ref "U4") (pin "30") (pinfunction "BSPR_30") (pintype "passive"))
    )
    (net (code "85") (name "Net-(U4-GAIN{slash}SLV)") (class "Default")
      (node (ref "R34") (pin "2") (pinfunction "2_2") (pintype "passive"))
      (node (ref "R36") (pin "2") (pinfunction "2_2") (pintype "passive"))
      (node (ref "U4") (pin "8") (pinfunction "GAIN/SLV_8") (pintype "input"))
    )
    (net (code "86") (name "Net-(U4-SYNC)") (class "Default")
      (node (ref "R37") (pin "2") (pinfunction "2_2") (pintype "passive"))
      (node (ref "U4") (pin "16") (pinfunction "SYNC_16") (pintype "bidirectional"))
    )
    (net (code "87") (name "PVCC") (class "Default")
      (node (ref "C10") (pin "1") (pinfunction "1_1") (pintype "passive"))
      (node (ref "C26") (pin "1") (pinfunction "+_1") (pintype "passive"))
      (node (ref "C27") (pin "2") (pinfunction "2_2") (pintype "passive"))
      (node (ref "C28") (pin "2") (pinfunction "2_2") (pintype "passive"))
      (node (ref "C32") (pin "1") (pinfunction "+_1") (pintype "passive"))
      (node (ref "C33") (pin "2") (pinfunction "2_2") (pintype "passive"))
      (node (ref "C34") (pin "2") (pinfunction "2_2") (pintype "passive"))
      (node (ref "C5") (pin "1") (pinfunction "1_1") (pintype "passive"))
      (node (ref "C7") (pin "1") (pinfunction "1_1") (pintype "passive"))
      (node (ref "C8") (pin "1") (pinfunction "1_1") (pintype "passive"))
      (node (ref "C9") (pin "1") (pinfunction "1_1") (pintype "passive"))
      (node (ref "J3") (pin "1") (pintype "passive"))
      (node (ref "J9") (pin "3") (pinfunction "3_3") (pintype "passive"))
      (node (ref "Q1") (pin "1") (pinfunction "VIN_1") (pintype "passive"))
      (node (ref "Q1") (pin "2") (pinfunction "VIN_2") (pintype "passive"))
      (node (ref "R31") (pin "2") (pinfunction "2_2") (pintype "passive"))
      (node (ref "R38") (pin "1") (pinfunction "1_1") (pintype "passive"))
      (node (ref "R39") (pin "2") (pinfunction "2_2") (pintype "passive"))
      (node (ref "R4") (pin "2") (pinfunction "2_2") (pintype "passive"))
      (node (ref "R41") (pin "1") (pinfunction "1_1") (pintype "passive"))
      (node (ref "U4") (pin "18") (pinfunction "PVCC_18") (pintype "power_in"))
      (node (ref "U4") (pin "19") (pinfunction "PVCC_19") (pintype "power_in"))
      (node (ref "U4") (pin "31") (pinfunction "PVCC_31") (pintype "power_in"))
      (node (ref "U4") (pin "32") (pinfunction "PVCC_32") (pintype "power_in"))
    )
    (net (code "88") (name "VCC") (class "Default")
      (node (ref "C12") (pin "1") (pinfunction "1_1") (pintype "passive"))
      (node (ref "R8") (pin "1") (pinfunction "1_1") (pintype "passive"))
      (node (ref "U2") (pin "10") (pinfunction "VCC_10") (pintype "power_in"))
    )
    (net (code "89") (name "Vin") (class "Default")
      (node (ref "C3") (pin "1") (pinfunction "+_1") (pintype "passive"))
      (node (ref "C4") (pin "1") (pinfunction "1_1") (pintype "passive"))
      (node (ref "J1") (pin "1") (pintype "passive"))
      (node (ref "J4") (pin "3") (pinfunction "3_3") (pintype "passive"))
      (node (ref "JP1") (pin "2") (pinfunction "2_2") (pintype "passive"))
      (node (ref "R1") (pin "1") (pinfunction "1_1") (pintype "passive"))
      (node (ref "R2") (pin "2") (pinfunction "2_2") (pintype "passive"))
    )
    (net (code "90") (name "unconnected-(D1-NC-Pad2)") (class "Default")
      (node (ref "D1") (pin "2") (pinfunction "NC_2") (pintype "passive"))
    )
    (net (code "91") (name "unconnected-(U3B-V+-Pad4)") (class "Default")
      (node (ref "U3") (pin "4") (pinfunction "V+_4") (pintype "power_in"))
    )
    (net (code "92") (name "unconnected-(U3C-V+-Pad4)") (class "Default")
      (node (ref "U3") (pin "4") (pinfunction "V+_4") (pintype "power_in"))
    )
    (net (code "93") (name "unconnected-(U3C-V--Pad11)") (class "Default")
      (node (ref "U3") (pin "11") (pinfunction "V-_11") (pintype "power_in"))
    )
    (net (code "94") (name "unconnected-(U3D-V+-Pad4)") (class "Default")
      (node (ref "U3") (pin "4") (pinfunction "V+_4") (pintype "power_in"))
    )
    (net (code "95") (name "unconnected-(U3D-V--Pad11)") (class "Default")
      (node (ref "U3") (pin "11") (pinfunction "V-_11") (pintype "power_in"))
    )
  )
)
